# XMICRO-MEMORY.net
KiCad netlist of a schematic drawn in EAGLE
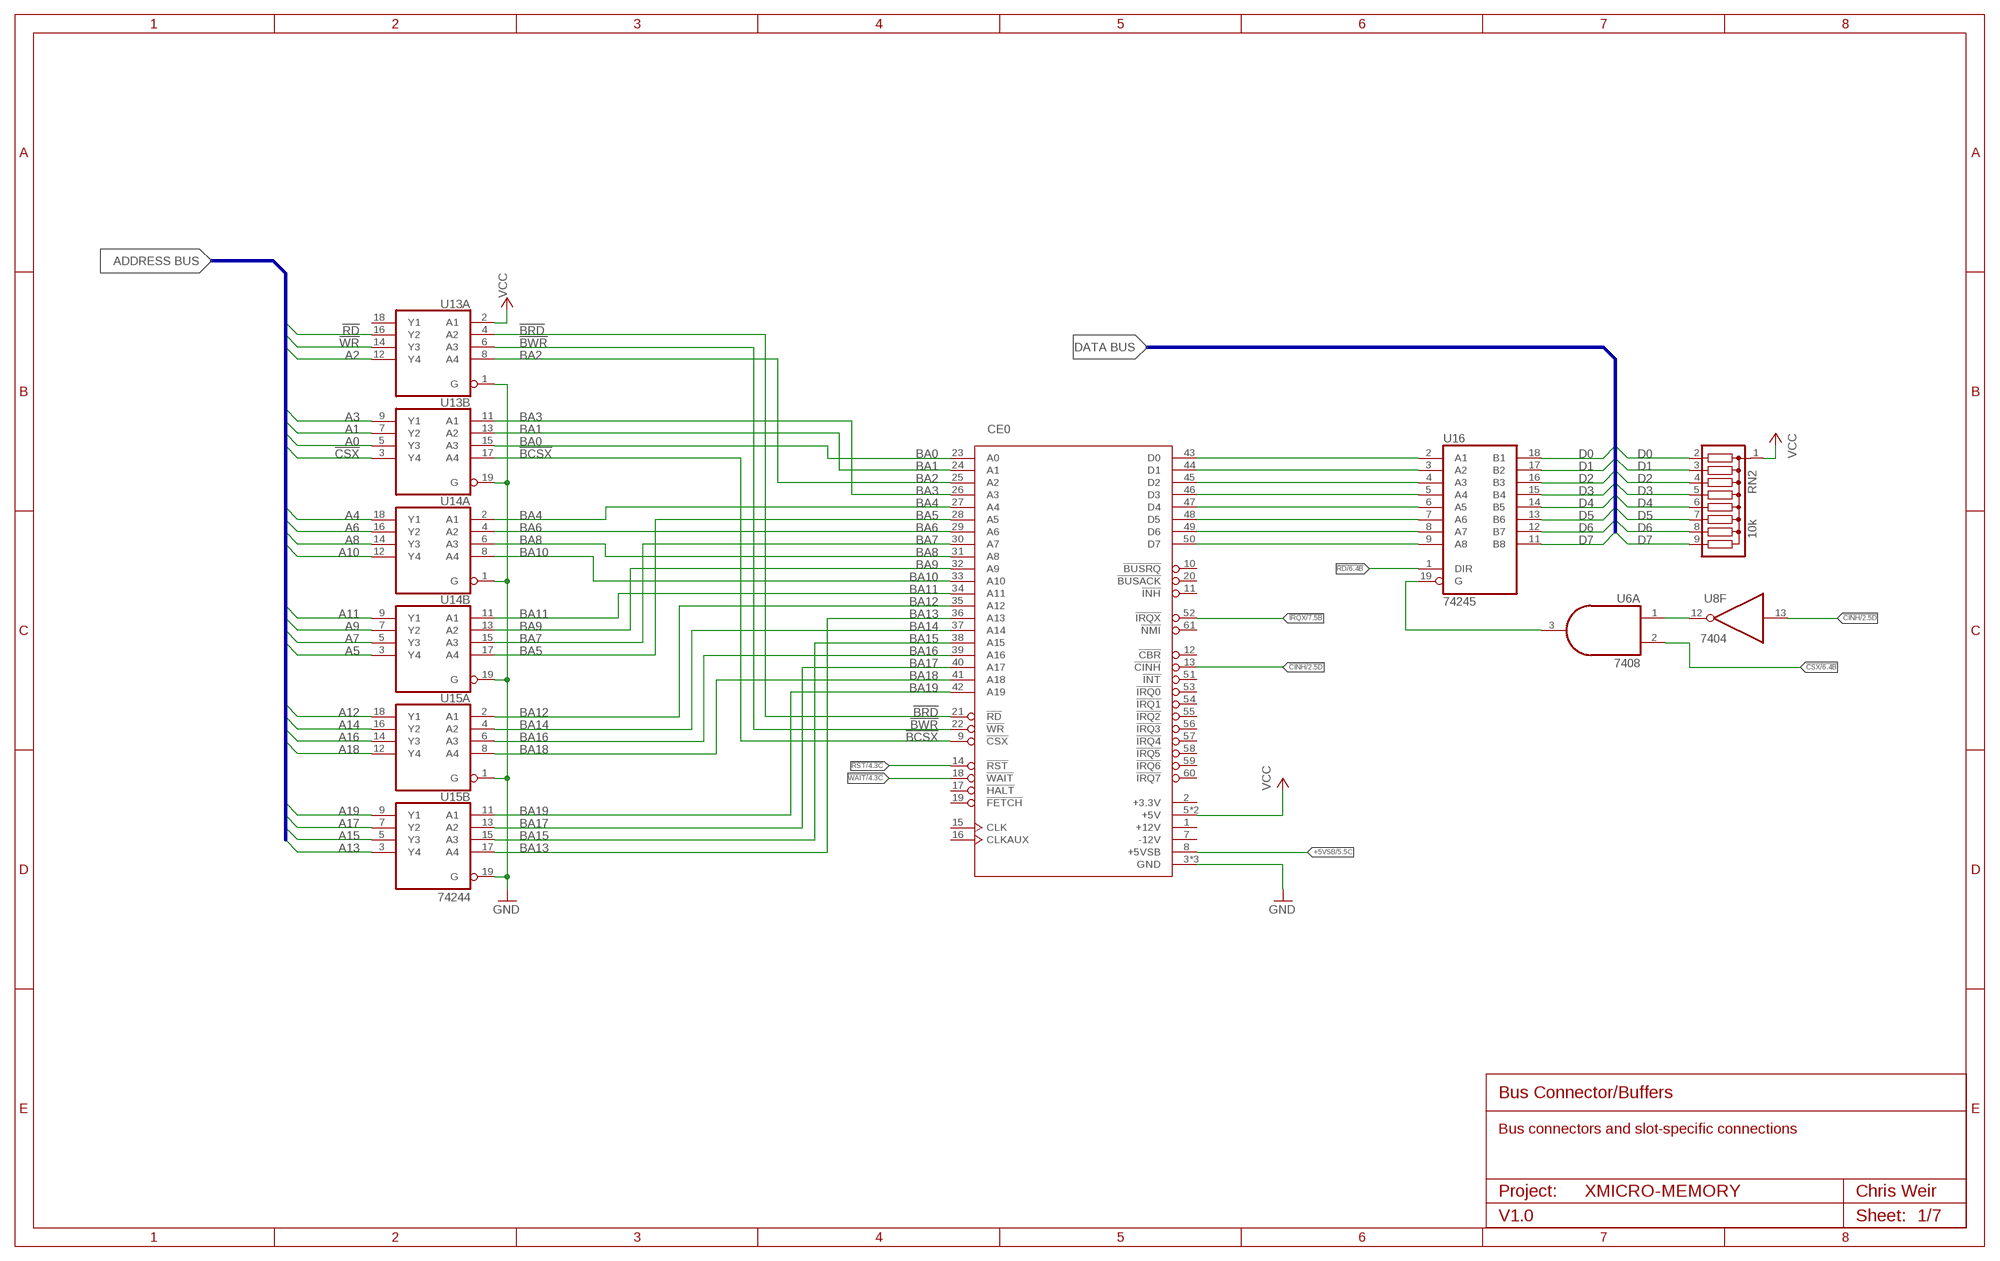
[diagram p0: schematic, sheet 1]
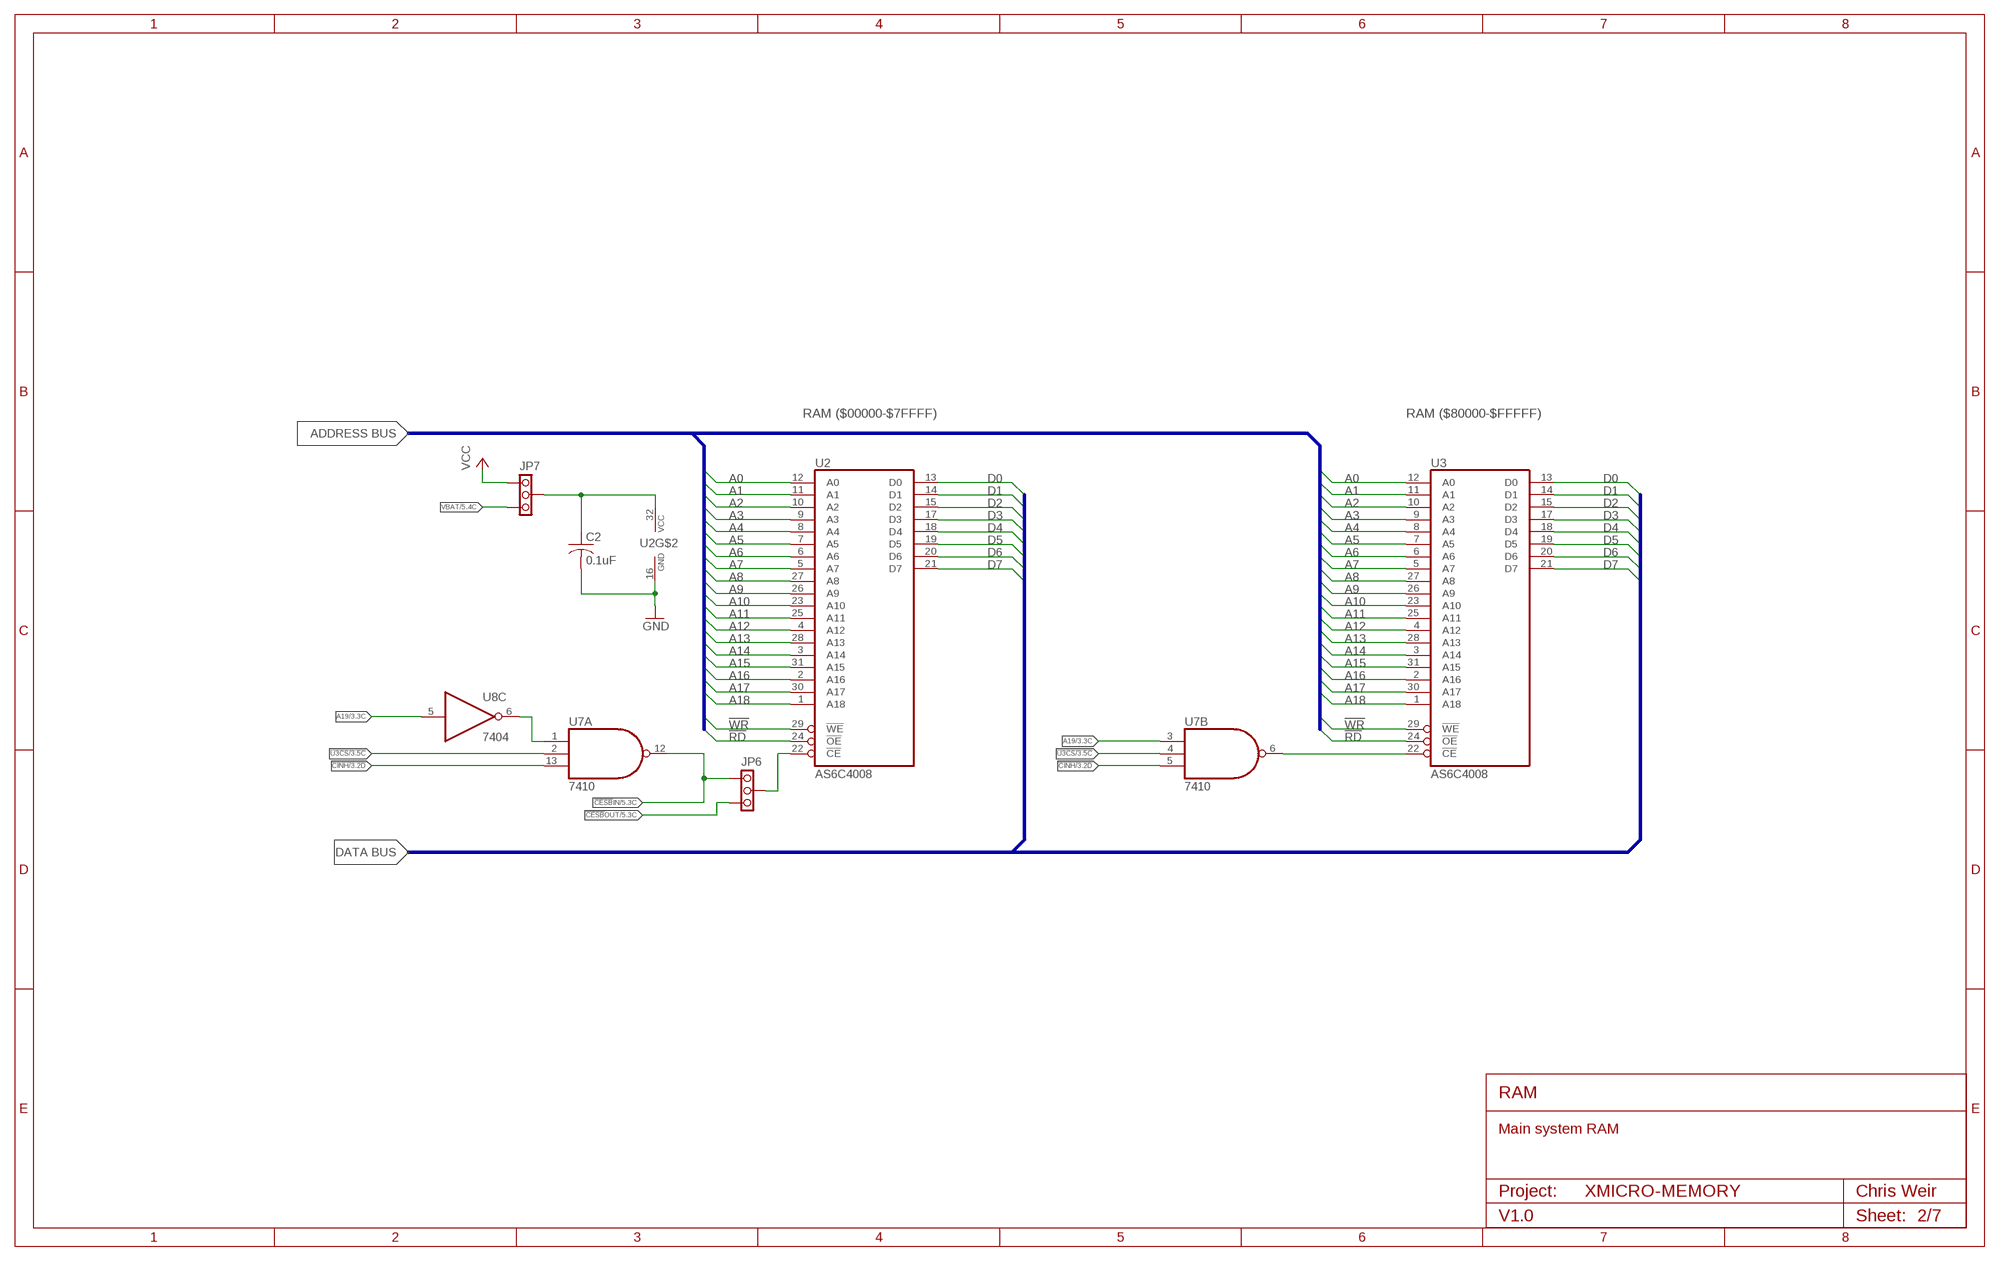
[diagram p1: schematic, sheet 2]
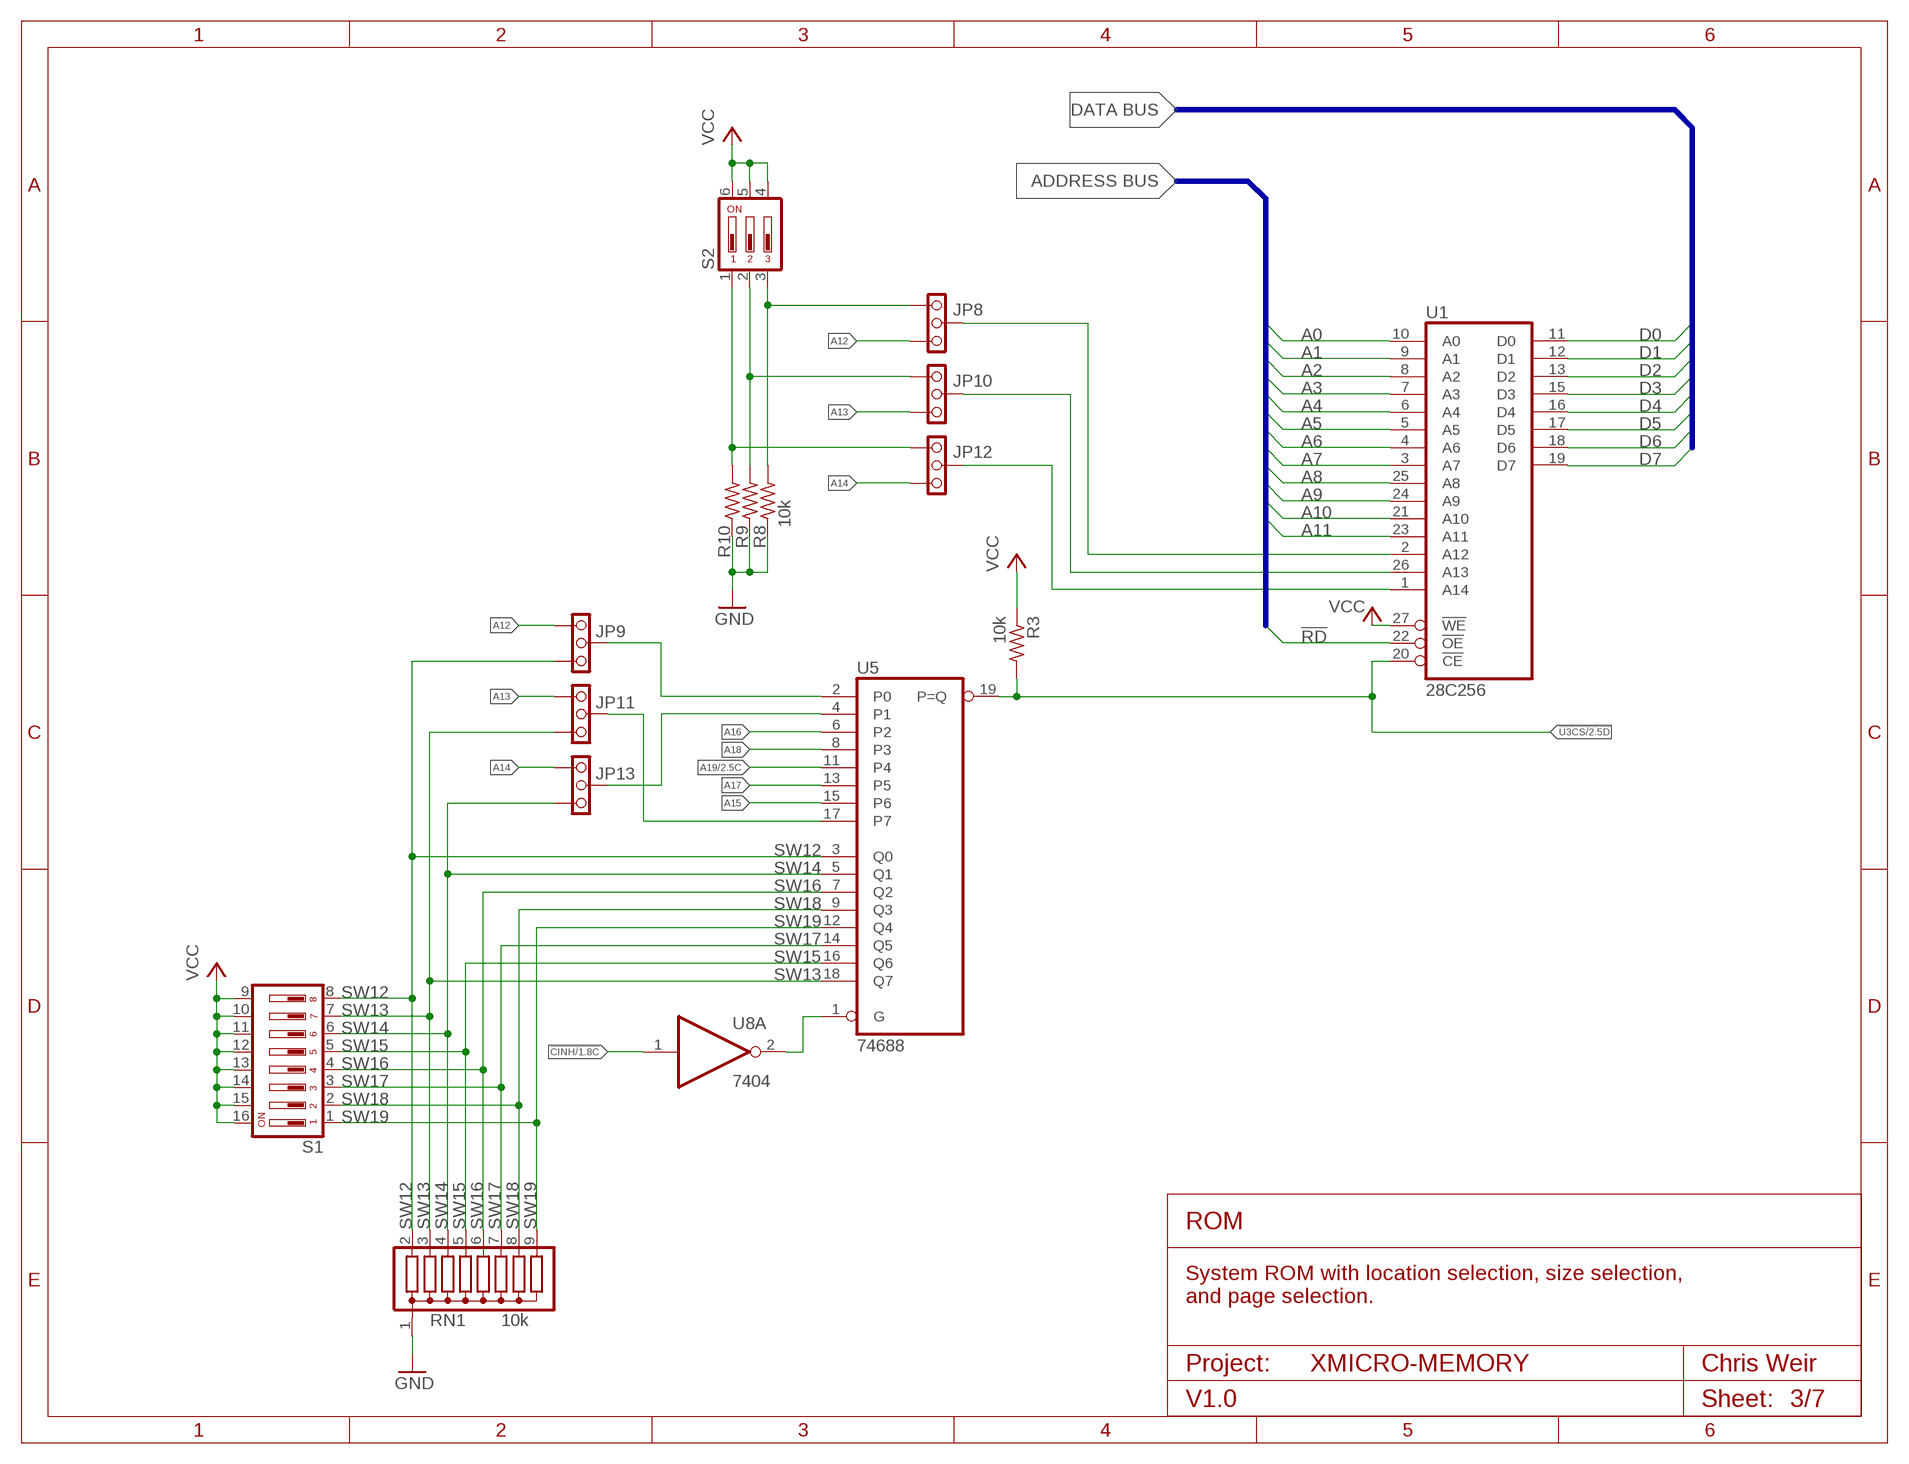
[diagram p2: schematic, sheet 3]
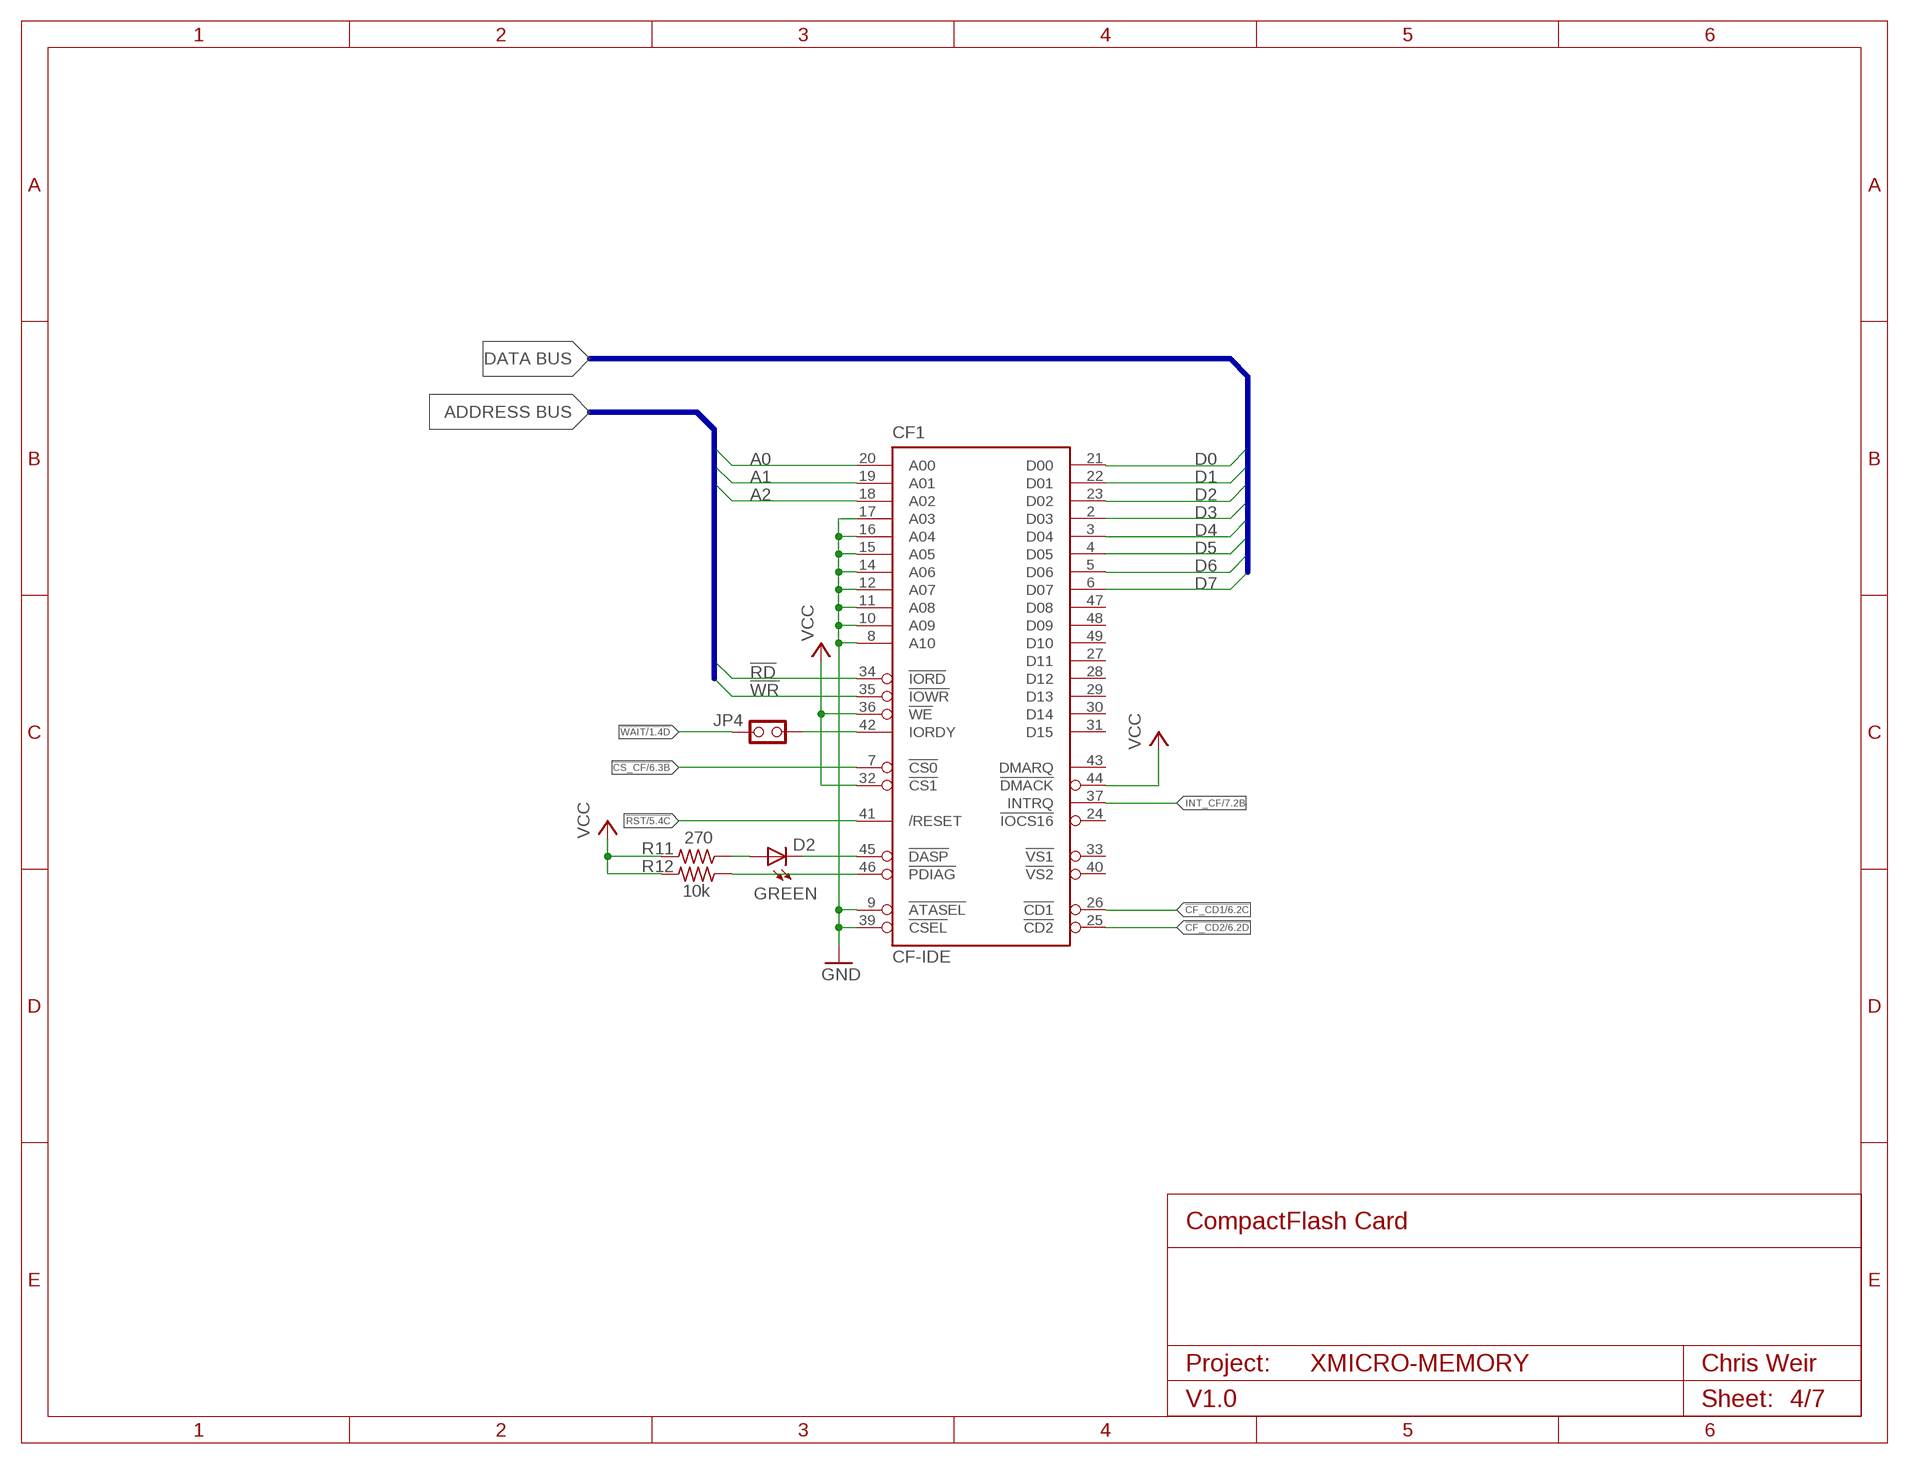
[diagram p3: schematic, sheet 4]
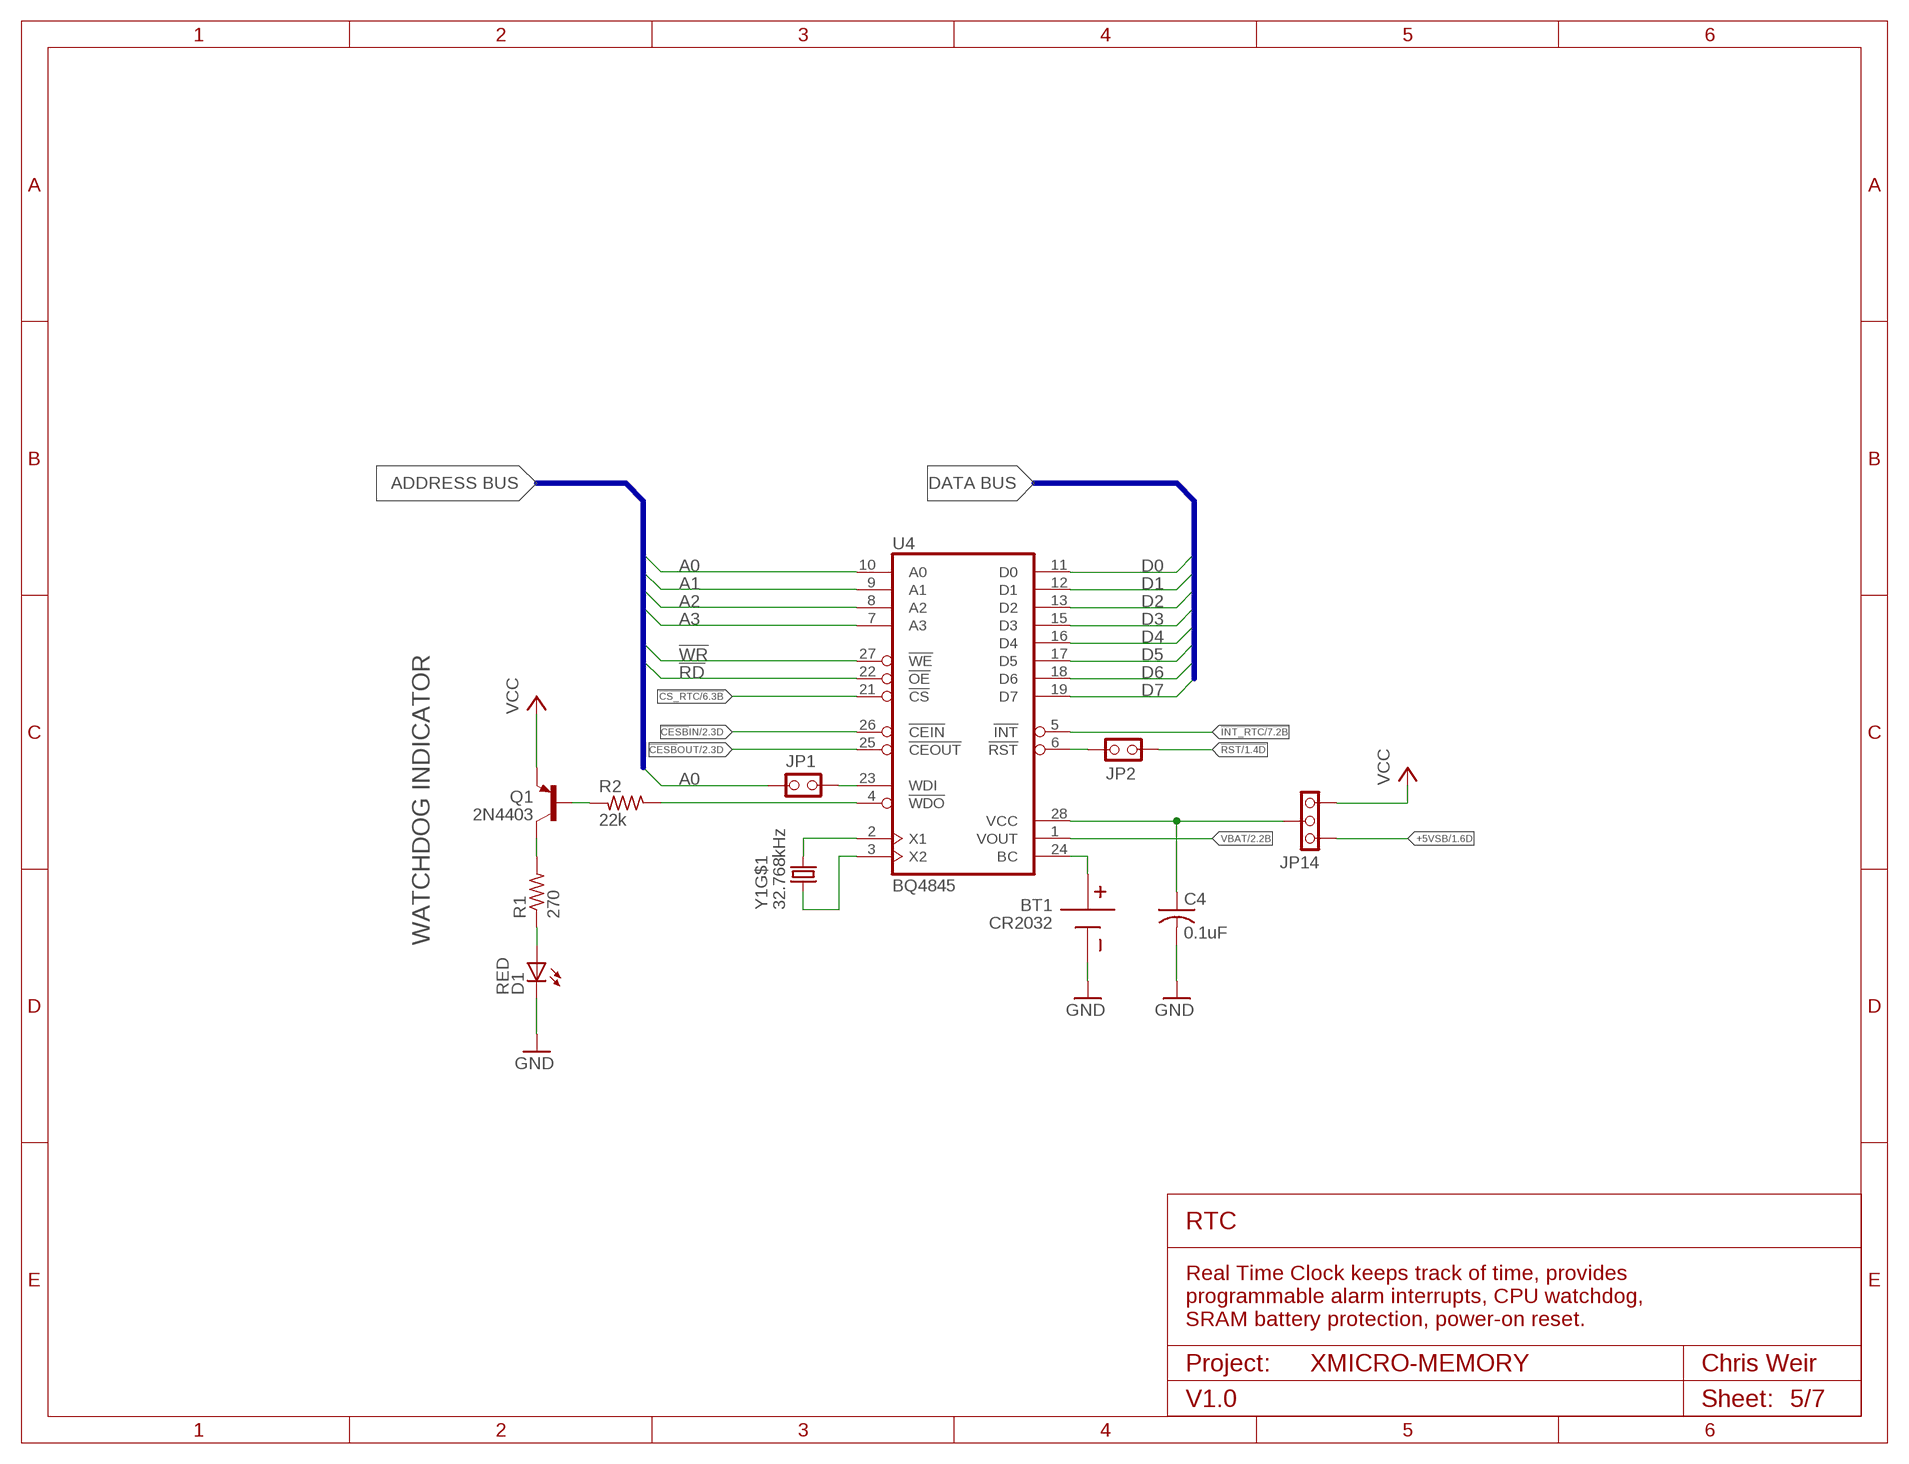
[diagram p4: schematic, sheet 5]
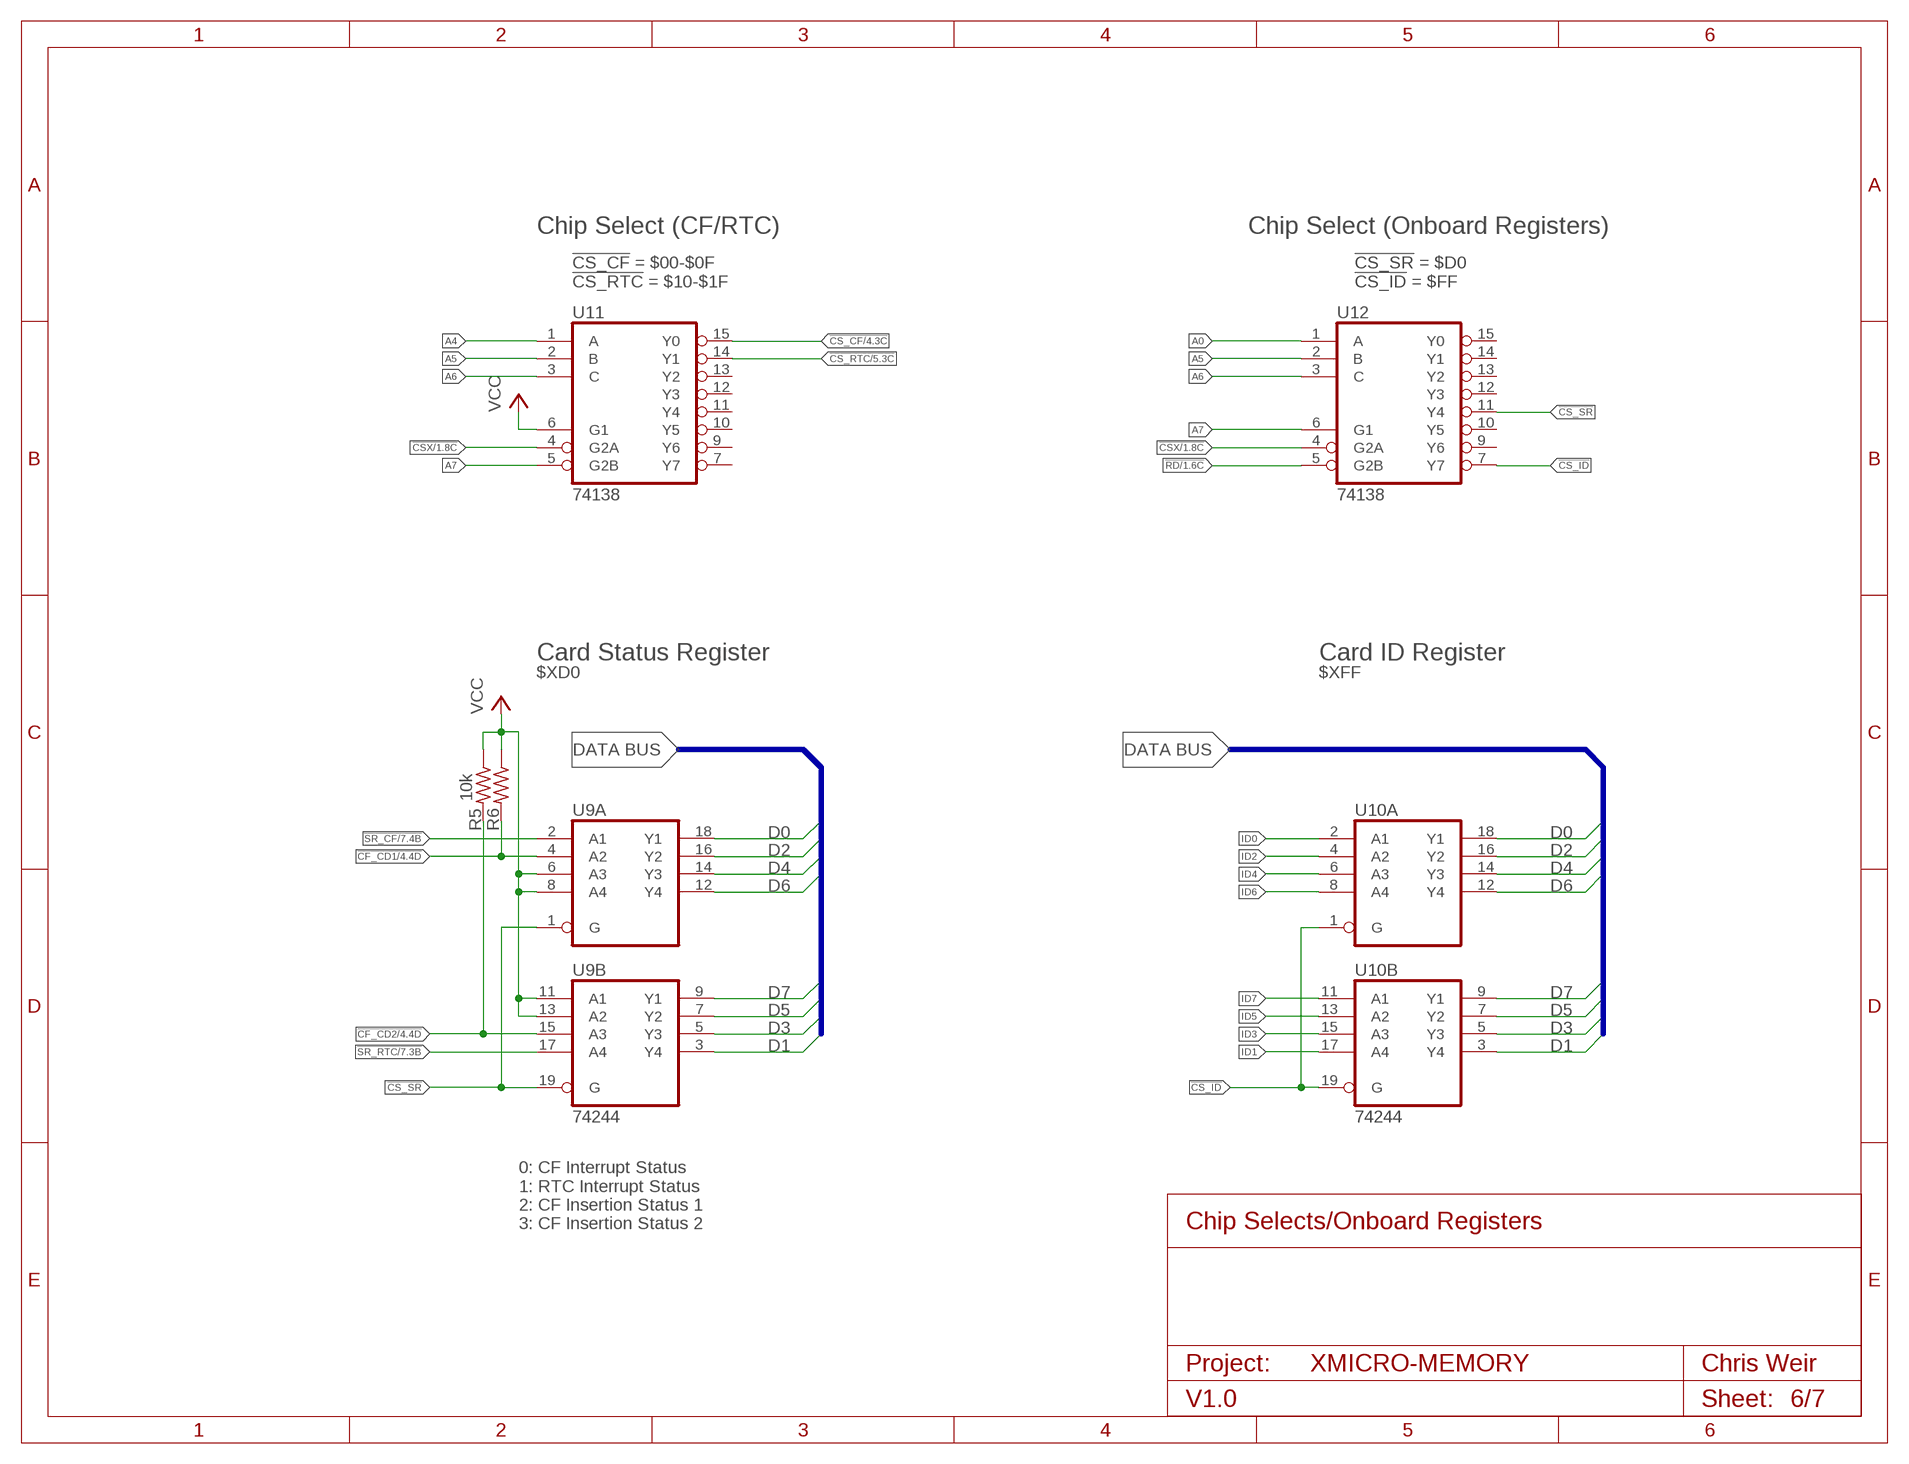
[diagram p5: schematic, sheet 6]
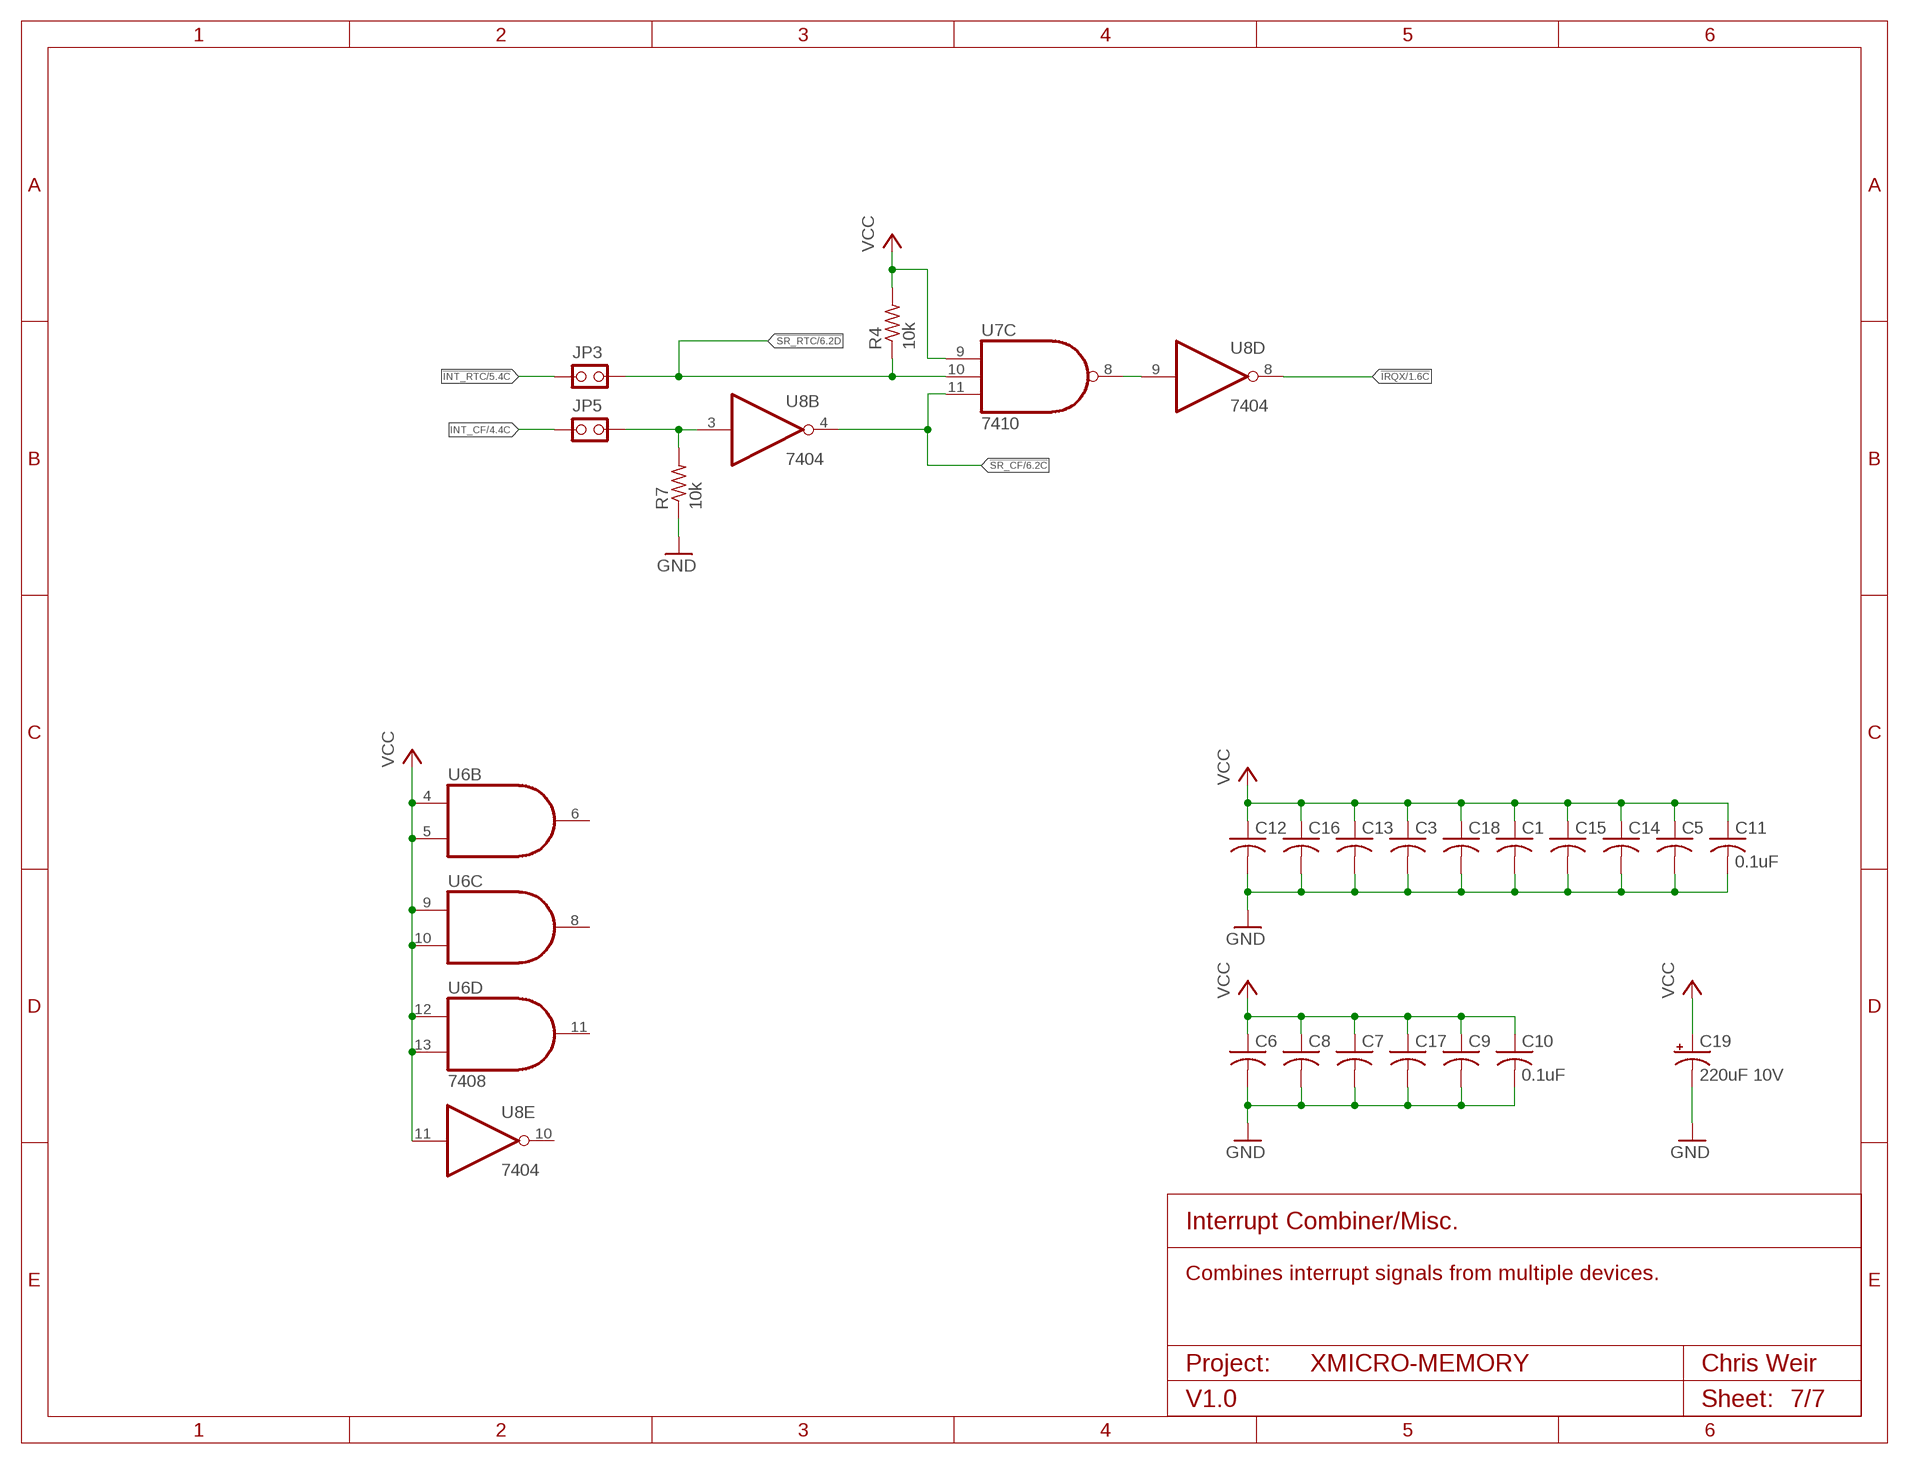
[diagram p6: schematic, sheet 7]

(export (version "E")
  (design (tool "Eeschema 10.0.6"))
  (components
    (comp (ref "BT1")
      (value "CR2032")
      (footprint "eagle-import:SMTU2032")
      (libsource (lib "eagle-import") (part "CR2032SMT"))
    )
    (comp (ref "C4")
      (value "0.1uF")
      (footprint "eagle-import:C025-024X044")
      (libsource (lib "eagle-import") (part "C-US025-024X044"))
    )
    (comp (ref "D1")
      (value "RED")
      (footprint "eagle-import:LED5MM")
      (libsource (lib "eagle-import") (part "LED5MM"))
    )
    (comp (ref "JP1")
      (value "PINHD-1X2THRU")
      (footprint "eagle-import:1X02")
      (libsource (lib "eagle-import") (part "PINHD-1X2THRU"))
    )
    (comp (ref "JP2")
      (value "PINHD-1X2THRU")
      (footprint "eagle-import:1X02")
      (libsource (lib "eagle-import") (part "PINHD-1X2THRU"))
    )
    (comp (ref "JP14")
      (value "PINHD1X3THRU")
      (footprint "eagle-import:1X03")
      (libsource (lib "eagle-import") (part "PINHD1X3THRU"))
    )
    (comp (ref "Q1")
      (value "2N4403")
      (footprint "eagle-import:TO92")
      (libsource (lib "eagle-import") (part "TRANSISTOR-PNP-2N4403"))
    )
    (comp (ref "R1")
      (value "270")
      (footprint "eagle-import:0207_10")
      (libsource (lib "eagle-import") (part "R-US_0207/10"))
    )
    (comp (ref "R2")
      (value "22k")
      (footprint "eagle-import:0207_10")
      (libsource (lib "eagle-import") (part "R-US_0207/10"))
    )
    (comp (ref "U4")
      (value "BQ4845")
      (footprint "eagle-import:DIL28")
      (libsource (lib "eagle-import") (part "BQ4845"))
    )
    (comp (ref "Y1")
      (value "32.768kHz")
      (footprint "eagle-import:CRYSTAL-3X8H")
      (libsource (lib "eagle-import") (part "CRYSTAL"))
    )
    (comp (ref "R5")
      (value "10k")
      (footprint "eagle-import:0207_10")
      (libsource (lib "eagle-import") (part "R-US_0207/10"))
    )
    (comp (ref "R6")
      (value "10k")
      (footprint "eagle-import:0207_10")
      (libsource (lib "eagle-import") (part "R-US_0207/10"))
    )
    (comp (ref "U9")
      (value "74244")
      (footprint "eagle-import:DIL20")
      (libsource (lib "eagle-import") (part "74244NLS"))
    )
    (comp (ref "U10")
      (value "74244")
      (footprint "eagle-import:DIL20")
      (libsource (lib "eagle-import") (part "74244NLS"))
    )
    (comp (ref "U11")
      (value "74138")
      (footprint "eagle-import:DIL16")
      (libsource (lib "eagle-import") (part "74138NLS"))
    )
    (comp (ref "U12")
      (value "74138")
      (footprint "eagle-import:DIL16")
      (libsource (lib "eagle-import") (part "74138NLS"))
    )
    (comp (ref "C1")
      (value "0.1uF")
      (footprint "eagle-import:C025-024X044")
      (libsource (lib "eagle-import") (part "C-US025-024X044"))
    )
    (comp (ref "C3")
      (value "0.1uF")
      (footprint "eagle-import:C025-024X044")
      (libsource (lib "eagle-import") (part "C-US025-024X044"))
    )
    (comp (ref "C5")
      (value "0.1uF")
      (footprint "eagle-import:C025-024X044")
      (libsource (lib "eagle-import") (part "C-US025-024X044"))
    )
    (comp (ref "C6")
      (value "0.1uF")
      (footprint "eagle-import:C025-024X044")
      (libsource (lib "eagle-import") (part "C-US025-024X044"))
    )
    (comp (ref "C7")
      (value "0.1uF")
      (footprint "eagle-import:C025-024X044")
      (libsource (lib "eagle-import") (part "C-US025-024X044"))
    )
    (comp (ref "C8")
      (value "0.1uF")
      (footprint "eagle-import:C025-024X044")
      (libsource (lib "eagle-import") (part "C-US025-024X044"))
    )
    (comp (ref "C9")
      (value "0.1uF")
      (footprint "eagle-import:C025-024X044")
      (libsource (lib "eagle-import") (part "C-US025-024X044"))
    )
    (comp (ref "C10")
      (value "0.1uF")
      (footprint "eagle-import:C025-024X044")
      (libsource (lib "eagle-import") (part "C-US025-024X044"))
    )
    (comp (ref "C11")
      (value "0.1uF")
      (footprint "eagle-import:C025-024X044")
      (libsource (lib "eagle-import") (part "C-US025-024X044"))
    )
    (comp (ref "C12")
      (value "0.1uF")
      (footprint "eagle-import:C025-024X044")
      (libsource (lib "eagle-import") (part "C-US025-024X044"))
    )
    (comp (ref "C13")
      (value "0.1uF")
      (footprint "eagle-import:C025-024X044")
      (libsource (lib "eagle-import") (part "C-US025-024X044"))
    )
    (comp (ref "C14")
      (value "0.1uF")
      (footprint "eagle-import:C025-024X044")
      (libsource (lib "eagle-import") (part "C-US025-024X044"))
    )
    (comp (ref "C15")
      (value "0.1uF")
      (footprint "eagle-import:C025-024X044")
      (libsource (lib "eagle-import") (part "C-US025-024X044"))
    )
    (comp (ref "C16")
      (value "0.1uF")
      (footprint "eagle-import:C025-024X044")
      (libsource (lib "eagle-import") (part "C-US025-024X044"))
    )
    (comp (ref "C17")
      (value "0.1uF")
      (footprint "eagle-import:C025-024X044")
      (libsource (lib "eagle-import") (part "C-US025-024X044"))
    )
    (comp (ref "C18")
      (value "0.1uF")
      (footprint "eagle-import:C025-024X044")
      (libsource (lib "eagle-import") (part "C-US025-024X044"))
    )
    (comp (ref "C19")
      (value "220uF 10V")
      (footprint "eagle-import:C-10-5")
      (libsource (lib "eagle-import") (part "CPOL-US-10-5"))
    )
    (comp (ref "JP3")
      (value "PINHD-1X2THRU")
      (footprint "eagle-import:1X02")
      (libsource (lib "eagle-import") (part "PINHD-1X2THRU"))
    )
    (comp (ref "JP5")
      (value "PINHD-1X2THRU")
      (footprint "eagle-import:1X02")
      (libsource (lib "eagle-import") (part "PINHD-1X2THRU"))
    )
    (comp (ref "R4")
      (value "10k")
      (footprint "eagle-import:0207_10")
      (libsource (lib "eagle-import") (part "R-US_0207/10"))
    )
    (comp (ref "R7")
      (value "10k")
      (footprint "eagle-import:0207_10")
      (libsource (lib "eagle-import") (part "R-US_0207/10"))
    )
    (comp (ref "U6")
      (value "7408")
      (footprint "eagle-import:DIL14")
      (libsource (lib "eagle-import") (part "7408NLS"))
    )
    (comp (ref "U7")
      (value "7410")
      (footprint "eagle-import:DIL14")
      (libsource (lib "eagle-import") (part "7410NLS"))
    )
    (comp (ref "U8")
      (value "7404")
      (footprint "eagle-import:DIL14")
      (libsource (lib "eagle-import") (part "7404NLS"))
    )
    (comp (ref "C2")
      (value "0.1uF")
      (footprint "eagle-import:C025-024X044")
      (libsource (lib "eagle-import") (part "C-US025-024X044"))
    )
    (comp (ref "JP6")
      (value "PINHD1X3THRU")
      (footprint "eagle-import:1X03")
      (libsource (lib "eagle-import") (part "PINHD1X3THRU"))
    )
    (comp (ref "JP7")
      (value "PINHD1X3THRU")
      (footprint "eagle-import:1X03")
      (libsource (lib "eagle-import") (part "PINHD1X3THRU"))
    )
    (comp (ref "U2")
      (value "AS6C4008")
      (footprint "eagle-import:DIL32-6")
      (libsource (lib "eagle-import") (part "4008"))
    )
    (comp (ref "U3")
      (value "AS6C4008")
      (footprint "eagle-import:DIL32-6")
      (libsource (lib "eagle-import") (part "4008"))
    )
    (comp (ref "JP8")
      (value "PINHD1X3THRU")
      (footprint "eagle-import:1X03")
      (libsource (lib "eagle-import") (part "PINHD1X3THRU"))
    )
    (comp (ref "JP9")
      (value "PINHD1X3THRU")
      (footprint "eagle-import:1X03")
      (libsource (lib "eagle-import") (part "PINHD1X3THRU"))
    )
    (comp (ref "JP10")
      (value "PINHD1X3THRU")
      (footprint "eagle-import:1X03")
      (libsource (lib "eagle-import") (part "PINHD1X3THRU"))
    )
    (comp (ref "JP11")
      (value "PINHD1X3THRU")
      (footprint "eagle-import:1X03")
      (libsource (lib "eagle-import") (part "PINHD1X3THRU"))
    )
    (comp (ref "JP12")
      (value "PINHD1X3THRU")
      (footprint "eagle-import:1X03")
      (libsource (lib "eagle-import") (part "PINHD1X3THRU"))
    )
    (comp (ref "JP13")
      (value "PINHD1X3THRU")
      (footprint "eagle-import:1X03")
      (libsource (lib "eagle-import") (part "PINHD1X3THRU"))
    )
    (comp (ref "R3")
      (value "10k")
      (footprint "eagle-import:0207_10")
      (libsource (lib "eagle-import") (part "R-US_0207/10"))
    )
    (comp (ref "R8")
      (value "10k")
      (footprint "eagle-import:0207_10")
      (libsource (lib "eagle-import") (part "R-US_0207/10"))
    )
    (comp (ref "R9")
      (value "10k")
      (footprint "eagle-import:0207_10")
      (libsource (lib "eagle-import") (part "R-US_0207/10"))
    )
    (comp (ref "R10")
      (value "10k")
      (footprint "eagle-import:0207_10")
      (libsource (lib "eagle-import") (part "R-US_0207/10"))
    )
    (comp (ref "RN1")
      (value "10k")
      (footprint "eagle-import:SIL9")
      (libsource (lib "eagle-import") (part "G08R"))
    )
    (comp (ref "S1")
      (value "SW-DIP08")
      (footprint "eagle-import:SW-DIP8")
      (libsource (lib "eagle-import") (part "SW-DIP08"))
    )
    (comp (ref "S2")
      (value "SW-DIP03")
      (footprint "eagle-import:SW-DIP3")
      (libsource (lib "eagle-import") (part "SW-DIP03"))
    )
    (comp (ref "U1")
      (value "28C256")
      (footprint "eagle-import:228-1277-00")
      (libsource (lib "eagle-import") (part "28256-ZIF28"))
    )
    (comp (ref "U5")
      (value "74688")
      (footprint "eagle-import:DIL20")
      (libsource (lib "eagle-import") (part "74688NLS"))
    )
    (comp (ref "CF1")
      (value "CF-IDE")
      (footprint "eagle-import:CF-KYOCERA")
      (libsource (lib "eagle-import") (part "CF-IDE"))
    )
    (comp (ref "D2")
      (value "GREEN")
      (footprint "eagle-import:LED-3-R")
      (libsource (lib "eagle-import") (part "LED-3-R"))
    )
    (comp (ref "JP4")
      (value "PINHD-1X2THRU")
      (footprint "eagle-import:1X02")
      (libsource (lib "eagle-import") (part "PINHD-1X2THRU"))
    )
    (comp (ref "R11")
      (value "270")
      (footprint "eagle-import:0207_10")
      (libsource (lib "eagle-import") (part "R-US_0207/10"))
    )
    (comp (ref "R12")
      (value "10k")
      (footprint "eagle-import:0207_10")
      (libsource (lib "eagle-import") (part "R-US_0207/10"))
    )
    (comp (ref "CE0")
      (value "XMICRO-BUS-EDGE62M")
      (footprint "eagle-import:EDGE62M")
      (libsource (lib "eagle-import") (part "XMICRO-BUS-EDGE62M"))
    )
    (comp (ref "RN2")
      (value "10k")
      (footprint "eagle-import:SIL9")
      (fields (field (name "OC_FARNELL") "unknown") (field (name "OC_NEWARK") "unknown"))
      (libsource (lib "eagle-import") (part "G08R"))
    )
    (comp (ref "U13")
      (value "74244")
      (footprint "eagle-import:DIL20")
      (libsource (lib "eagle-import") (part "74244NLS"))
    )
    (comp (ref "U14")
      (value "74244")
      (footprint "eagle-import:DIL20")
      (libsource (lib "eagle-import") (part "74244NLS"))
    )
    (comp (ref "U15")
      (value "74244")
      (footprint "eagle-import:DIL20")
      (libsource (lib "eagle-import") (part "74244NLS"))
    )
    (comp (ref "U16")
      (value "74245")
      (footprint "eagle-import:DIL20")
      (libsource (lib "eagle-import") (part "74245NLS"))
    )
  )
  (nets
    (net (code "1") (name "+5VSB") (class "Default")
      (node (ref "CE0") (pin "8") (pinfunction "+5VSB_8") (pintype "bidirectional"))
      (node (ref "JP14") (pin "1") (pinfunction "1_1") (pintype "passive"))
    )
    (net (code "3") (name "A0") (class "Default")
      (node (ref "CF1") (pin "20") (pinfunction "A00_20") (pintype "input"))
      (node (ref "JP1") (pin "1") (pinfunction "1_1") (pintype "passive"))
      (node (ref "U1") (pin "10") (pinfunction "A0_10") (pintype "input"))
      (node (ref "U12") (pin "1") (pinfunction "A_1") (pintype "input"))
      (node (ref "U13") (pin "5") (pinfunction "Y3_5") (pintype "tri_state"))
      (node (ref "U2") (pin "12") (pinfunction "A0_12") (pintype "input"))
      (node (ref "U3") (pin "12") (pinfunction "A0_12") (pintype "input"))
      (node (ref "U4") (pin "10") (pinfunction "A0_10") (pintype "input"))
    )
    (net (code "4") (name "A1") (class "Default")
      (node (ref "CF1") (pin "19") (pinfunction "A01_19") (pintype "input"))
      (node (ref "U1") (pin "9") (pinfunction "A1_9") (pintype "input"))
      (node (ref "U13") (pin "7") (pinfunction "Y2_7") (pintype "tri_state"))
      (node (ref "U2") (pin "11") (pinfunction "A1_11") (pintype "input"))
      (node (ref "U3") (pin "11") (pinfunction "A1_11") (pintype "input"))
      (node (ref "U4") (pin "9") (pinfunction "A1_9") (pintype "input"))
    )
    (net (code "5") (name "A2") (class "Default")
      (node (ref "CF1") (pin "18") (pinfunction "A02_18") (pintype "input"))
      (node (ref "U1") (pin "8") (pinfunction "A2_8") (pintype "input"))
      (node (ref "U13") (pin "12") (pinfunction "Y4_12") (pintype "tri_state"))
      (node (ref "U2") (pin "10") (pinfunction "A2_10") (pintype "input"))
      (node (ref "U3") (pin "10") (pinfunction "A2_10") (pintype "input"))
      (node (ref "U4") (pin "8") (pinfunction "A2_8") (pintype "input"))
    )
    (net (code "6") (name "A3") (class "Default")
      (node (ref "U1") (pin "7") (pinfunction "A3_7") (pintype "input"))
      (node (ref "U13") (pin "9") (pinfunction "Y1_9") (pintype "tri_state"))
      (node (ref "U2") (pin "9") (pinfunction "A3_9") (pintype "input"))
      (node (ref "U3") (pin "9") (pinfunction "A3_9") (pintype "input"))
      (node (ref "U4") (pin "7") (pinfunction "A3_7") (pintype "input"))
    )
    (net (code "7") (name "A4") (class "Default")
      (node (ref "U1") (pin "6") (pinfunction "A4_6") (pintype "input"))
      (node (ref "U11") (pin "1") (pinfunction "A_1") (pintype "input"))
      (node (ref "U14") (pin "18") (pinfunction "Y1_18") (pintype "tri_state"))
      (node (ref "U2") (pin "8") (pinfunction "A4_8") (pintype "input"))
      (node (ref "U3") (pin "8") (pinfunction "A4_8") (pintype "input"))
    )
    (net (code "8") (name "A5") (class "Default")
      (node (ref "U1") (pin "5") (pinfunction "A5_5") (pintype "input"))
      (node (ref "U11") (pin "2") (pinfunction "B_2") (pintype "input"))
      (node (ref "U12") (pin "2") (pinfunction "B_2") (pintype "input"))
      (node (ref "U14") (pin "3") (pinfunction "Y4_3") (pintype "tri_state"))
      (node (ref "U2") (pin "7") (pinfunction "A5_7") (pintype "input"))
      (node (ref "U3") (pin "7") (pinfunction "A5_7") (pintype "input"))
    )
    (net (code "9") (name "A6") (class "Default")
      (node (ref "U1") (pin "4") (pinfunction "A6_4") (pintype "input"))
      (node (ref "U11") (pin "3") (pinfunction "C_3") (pintype "input"))
      (node (ref "U12") (pin "3") (pinfunction "C_3") (pintype "input"))
      (node (ref "U14") (pin "16") (pinfunction "Y2_16") (pintype "tri_state"))
      (node (ref "U2") (pin "6") (pinfunction "A6_6") (pintype "input"))
      (node (ref "U3") (pin "6") (pinfunction "A6_6") (pintype "input"))
    )
    (net (code "10") (name "A7") (class "Default")
      (node (ref "U1") (pin "3") (pinfunction "A7_3") (pintype "input"))
      (node (ref "U11") (pin "5") (pinfunction "G2B_5") (pintype "input"))
      (node (ref "U12") (pin "6") (pinfunction "G1_6") (pintype "input"))
      (node (ref "U14") (pin "5") (pinfunction "Y3_5") (pintype "tri_state"))
      (node (ref "U2") (pin "5") (pinfunction "A7_5") (pintype "input"))
      (node (ref "U3") (pin "5") (pinfunction "A7_5") (pintype "input"))
    )
    (net (code "11") (name "A8") (class "Default")
      (node (ref "U1") (pin "25") (pinfunction "A8_25") (pintype "input"))
      (node (ref "U14") (pin "14") (pinfunction "Y3_14") (pintype "tri_state"))
      (node (ref "U2") (pin "27") (pinfunction "A8_27") (pintype "input"))
      (node (ref "U3") (pin "27") (pinfunction "A8_27") (pintype "input"))
    )
    (net (code "12") (name "A9") (class "Default")
      (node (ref "U1") (pin "24") (pinfunction "A9_24") (pintype "input"))
      (node (ref "U14") (pin "7") (pinfunction "Y2_7") (pintype "tri_state"))
      (node (ref "U2") (pin "26") (pinfunction "A9_26") (pintype "input"))
      (node (ref "U3") (pin "26") (pinfunction "A9_26") (pintype "input"))
    )
    (net (code "13") (name "A10") (class "Default")
      (node (ref "U1") (pin "21") (pinfunction "A10_21") (pintype "input"))
      (node (ref "U14") (pin "12") (pinfunction "Y4_12") (pintype "tri_state"))
      (node (ref "U2") (pin "23") (pinfunction "A10_23") (pintype "input"))
      (node (ref "U3") (pin "23") (pinfunction "A10_23") (pintype "input"))
    )
    (net (code "14") (name "A11") (class "Default")
      (node (ref "U1") (pin "23") (pinfunction "A11_23") (pintype "input"))
      (node (ref "U14") (pin "9") (pinfunction "Y1_9") (pintype "tri_state"))
      (node (ref "U2") (pin "25") (pinfunction "A11_25") (pintype "input"))
      (node (ref "U3") (pin "25") (pinfunction "A11_25") (pintype "input"))
    )
    (net (code "15") (name "A12") (class "Default")
      (node (ref "JP8") (pin "3") (pinfunction "3_3") (pintype "passive"))
      (node (ref "JP9") (pin "1") (pinfunction "1_1") (pintype "passive"))
      (node (ref "U15") (pin "18") (pinfunction "Y1_18") (pintype "tri_state"))
      (node (ref "U2") (pin "4") (pinfunction "A12_4") (pintype "input"))
      (node (ref "U3") (pin "4") (pinfunction "A12_4") (pintype "input"))
    )
    (net (code "16") (name "A13") (class "Default")
      (node (ref "JP10") (pin "3") (pinfunction "3_3") (pintype "passive"))
      (node (ref "JP11") (pin "1") (pinfunction "1_1") (pintype "passive"))
      (node (ref "U15") (pin "3") (pinfunction "Y4_3") (pintype "tri_state"))
      (node (ref "U2") (pin "28") (pinfunction "A13_28") (pintype "input"))
      (node (ref "U3") (pin "28") (pinfunction "A13_28") (pintype "input"))
    )
    (net (code "17") (name "A14") (class "Default")
      (node (ref "JP12") (pin "3") (pinfunction "3_3") (pintype "passive"))
      (node (ref "JP13") (pin "1") (pinfunction "1_1") (pintype "passive"))
      (node (ref "U15") (pin "16") (pinfunction "Y2_16") (pintype "tri_state"))
      (node (ref "U2") (pin "3") (pinfunction "A14_3") (pintype "input"))
      (node (ref "U3") (pin "3") (pinfunction "A14_3") (pintype "input"))
    )
    (net (code "18") (name "A15") (class "Default")
      (node (ref "U15") (pin "5") (pinfunction "Y3_5") (pintype "tri_state"))
      (node (ref "U2") (pin "31") (pinfunction "A15_31") (pintype "input"))
      (node (ref "U3") (pin "31") (pinfunction "A15_31") (pintype "input"))
      (node (ref "U5") (pin "15") (pinfunction "P6_15") (pintype "input"))
    )
    (net (code "19") (name "A16") (class "Default")
      (node (ref "U15") (pin "14") (pinfunction "Y3_14") (pintype "tri_state"))
      (node (ref "U2") (pin "2") (pinfunction "A16_2") (pintype "input"))
      (node (ref "U3") (pin "2") (pinfunction "A16_2") (pintype "input"))
      (node (ref "U5") (pin "6") (pinfunction "P2_6") (pintype "input"))
    )
    (net (code "20") (name "A17") (class "Default")
      (node (ref "U15") (pin "7") (pinfunction "Y2_7") (pintype "tri_state"))
      (node (ref "U2") (pin "30") (pinfunction "A17_30") (pintype "input"))
      (node (ref "U3") (pin "30") (pinfunction "A17_30") (pintype "input"))
      (node (ref "U5") (pin "13") (pinfunction "P5_13") (pintype "input"))
    )
    (net (code "21") (name "A18") (class "Default")
      (node (ref "U15") (pin "12") (pinfunction "Y4_12") (pintype "tri_state"))
      (node (ref "U2") (pin "1") (pinfunction "A18_1") (pintype "input"))
      (node (ref "U3") (pin "1") (pinfunction "A18_1") (pintype "input"))
      (node (ref "U5") (pin "8") (pinfunction "P3_8") (pintype "input"))
    )
    (net (code "22") (name "A19") (class "Default")
      (node (ref "U15") (pin "9") (pinfunction "Y1_9") (pintype "tri_state"))
      (node (ref "U5") (pin "11") (pinfunction "P4_11") (pintype "input"))
      (node (ref "U7") (pin "3") (pinfunction "I0_3") (pintype "input"))
      (node (ref "U8") (pin "5") (pinfunction "I_5") (pintype "input"))
    )
    (net (code "23") (name "BA0") (class "Default")
      (node (ref "CE0") (pin "23") (pinfunction "A0_23") (pintype "bidirectional"))
      (node (ref "U13") (pin "15") (pinfunction "A3_15") (pintype "input"))
    )
    (net (code "24") (name "BA1") (class "Default")
      (node (ref "CE0") (pin "24") (pinfunction "A1_24") (pintype "bidirectional"))
      (node (ref "U13") (pin "13") (pinfunction "A2_13") (pintype "input"))
    )
    (net (code "25") (name "BA2") (class "Default")
      (node (ref "CE0") (pin "25") (pinfunction "A2_25") (pintype "bidirectional"))
      (node (ref "U13") (pin "8") (pinfunction "A4_8") (pintype "input"))
    )
    (net (code "26") (name "BA3") (class "Default")
      (node (ref "CE0") (pin "26") (pinfunction "A3_26") (pintype "bidirectional"))
      (node (ref "U13") (pin "11") (pinfunction "A1_11") (pintype "input"))
    )
    (net (code "27") (name "BA4") (class "Default")
      (node (ref "CE0") (pin "27") (pinfunction "A4_27") (pintype "bidirectional"))
      (node (ref "U14") (pin "2") (pinfunction "A1_2") (pintype "input"))
    )
    (net (code "28") (name "BA5") (class "Default")
      (node (ref "CE0") (pin "28") (pinfunction "A5_28") (pintype "bidirectional"))
      (node (ref "U14") (pin "17") (pinfunction "A4_17") (pintype "input"))
    )
    (net (code "29") (name "BA6") (class "Default")
      (node (ref "CE0") (pin "29") (pinfunction "A6_29") (pintype "bidirectional"))
      (node (ref "U14") (pin "4") (pinfunction "A2_4") (pintype "input"))
    )
    (net (code "30") (name "BA7") (class "Default")
      (node (ref "CE0") (pin "30") (pinfunction "A7_30") (pintype "bidirectional"))
      (node (ref "U14") (pin "15") (pinfunction "A3_15") (pintype "input"))
    )
    (net (code "31") (name "BA8") (class "Default")
      (node (ref "CE0") (pin "31") (pinfunction "A8_31") (pintype "bidirectional"))
      (node (ref "U14") (pin "6") (pinfunction "A3_6") (pintype "input"))
    )
    (net (code "32") (name "BA9") (class "Default")
      (node (ref "CE0") (pin "32") (pinfunction "A9_32") (pintype "bidirectional"))
      (node (ref "U14") (pin "13") (pinfunction "A2_13") (pintype "input"))
    )
    (net (code "33") (name "BA10") (class "Default")
      (node (ref "CE0") (pin "33") (pinfunction "A10_33") (pintype "bidirectional"))
      (node (ref "U14") (pin "8") (pinfunction "A4_8") (pintype "input"))
    )
    (net (code "34") (name "BA11") (class "Default")
      (node (ref "CE0") (pin "34") (pinfunction "A11_34") (pintype "bidirectional"))
      (node (ref "U14") (pin "11") (pinfunction "A1_11") (pintype "input"))
    )
    (net (code "35") (name "BA12") (class "Default")
      (node (ref "CE0") (pin "35") (pinfunction "A12_35") (pintype "bidirectional"))
      (node (ref "U15") (pin "2") (pinfunction "A1_2") (pintype "input"))
    )
    (net (code "36") (name "BA13") (class "Default")
      (node (ref "CE0") (pin "36") (pinfunction "A13_36") (pintype "bidirectional"))
      (node (ref "U15") (pin "17") (pinfunction "A4_17") (pintype "input"))
    )
    (net (code "37") (name "BA14") (class "Default")
      (node (ref "CE0") (pin "37") (pinfunction "A14_37") (pintype "bidirectional"))
      (node (ref "U15") (pin "4") (pinfunction "A2_4") (pintype "input"))
    )
    (net (code "38") (name "BA15") (class "Default")
      (node (ref "CE0") (pin "38") (pinfunction "A15_38") (pintype "bidirectional"))
      (node (ref "U15") (pin "15") (pinfunction "A3_15") (pintype "input"))
    )
    (net (code "39") (name "BA16") (class "Default")
      (node (ref "CE0") (pin "39") (pinfunction "A16_39") (pintype "bidirectional"))
      (node (ref "U15") (pin "6") (pinfunction "A3_6") (pintype "input"))
    )
    (net (code "40") (name "BA17") (class "Default")
      (node (ref "CE0") (pin "40") (pinfunction "A17_40") (pintype "bidirectional"))
      (node (ref "U15") (pin "13") (pinfunction "A2_13") (pintype "input"))
    )
    (net (code "41") (name "BA18") (class "Default")
      (node (ref "CE0") (pin "41") (pinfunction "A18_41") (pintype "bidirectional"))
      (node (ref "U15") (pin "8") (pinfunction "A4_8") (pintype "input"))
    )
    (net (code "42") (name "BA19") (class "Default")
      (node (ref "CE0") (pin "42") (pinfunction "A19_42") (pintype "bidirectional"))
      (node (ref "U15") (pin "11") (pinfunction "A1_11") (pintype "input"))
    )
    (net (code "43") (name "D0") (class "Default")
      (node (ref "CF1") (pin "21") (pinfunction "D00_21") (pintype "tri_state"))
      (node (ref "RN2") (pin "2") (pinfunction "2_2") (pintype "passive"))
      (node (ref "U1") (pin "11") (pinfunction "D0_11") (pintype "tri_state"))
      (node (ref "U10") (pin "18") (pinfunction "Y1_18") (pintype "tri_state"))
      (node (ref "U16") (pin "18") (pinfunction "B1_18") (pintype "bidirectional"))
      (node (ref "U2") (pin "13") (pinfunction "D0_13") (pintype "tri_state"))
      (node (ref "U3") (pin "13") (pinfunction "D0_13") (pintype "tri_state"))
      (node (ref "U4") (pin "11") (pinfunction "D0_11") (pintype "tri_state"))
      (node (ref "U9") (pin "18") (pinfunction "Y1_18") (pintype "tri_state"))
    )
    (net (code "44") (name "D1") (class "Default")
      (node (ref "CF1") (pin "22") (pinfunction "D01_22") (pintype "tri_state"))
      (node (ref "RN2") (pin "3") (pinfunction "3_3") (pintype "passive"))
      (node (ref "U1") (pin "12") (pinfunction "D1_12") (pintype "tri_state"))
      (node (ref "U10") (pin "3") (pinfunction "Y4_3") (pintype "tri_state"))
      (node (ref "U16") (pin "17") (pinfunction "B2_17") (pintype "bidirectional"))
      (node (ref "U2") (pin "14") (pinfunction "D1_14") (pintype "tri_state"))
      (node (ref "U3") (pin "14") (pinfunction "D1_14") (pintype "tri_state"))
      (node (ref "U4") (pin "12") (pinfunction "D1_12") (pintype "tri_state"))
      (node (ref "U9") (pin "3") (pinfunction "Y4_3") (pintype "tri_state"))
    )
    (net (code "45") (name "D2") (class "Default")
      (node (ref "CF1") (pin "23") (pinfunction "D02_23") (pintype "tri_state"))
      (node (ref "RN2") (pin "4") (pinfunction "4_4") (pintype "passive"))
      (node (ref "U1") (pin "13") (pinfunction "D2_13") (pintype "tri_state"))
      (node (ref "U10") (pin "16") (pinfunction "Y2_16") (pintype "tri_state"))
      (node (ref "U16") (pin "16") (pinfunction "B3_16") (pintype "bidirectional"))
      (node (ref "U2") (pin "15") (pinfunction "D2_15") (pintype "tri_state"))
      (node (ref "U3") (pin "15") (pinfunction "D2_15") (pintype "tri_state"))
      (node (ref "U4") (pin "13") (pinfunction "D2_13") (pintype "tri_state"))
      (node (ref "U9") (pin "16") (pinfunction "Y2_16") (pintype "tri_state"))
    )
    (net (code "46") (name "D3") (class "Default")
      (node (ref "CF1") (pin "2") (pinfunction "D03_2") (pintype "tri_state"))
      (node (ref "RN2") (pin "5") (pinfunction "5_5") (pintype "passive"))
      (node (ref "U1") (pin "15") (pinfunction "D3_15") (pintype "tri_state"))
      (node (ref "U10") (pin "5") (pinfunction "Y3_5") (pintype "tri_state"))
      (node (ref "U16") (pin "15") (pinfunction "B4_15") (pintype "bidirectional"))
      (node (ref "U2") (pin "17") (pinfunction "D3_17") (pintype "tri_state"))
      (node (ref "U3") (pin "17") (pinfunction "D3_17") (pintype "tri_state"))
      (node (ref "U4") (pin "15") (pinfunction "D3_15") (pintype "tri_state"))
      (node (ref "U9") (pin "5") (pinfunction "Y3_5") (pintype "tri_state"))
    )
    (net (code "47") (name "D4") (class "Default")
      (node (ref "CF1") (pin "3") (pinfunction "D04_3") (pintype "tri_state"))
      (node (ref "RN2") (pin "6") (pinfunction "6_6") (pintype "passive"))
      (node (ref "U1") (pin "16") (pinfunction "D4_16") (pintype "tri_state"))
      (node (ref "U10") (pin "14") (pinfunction "Y3_14") (pintype "tri_state"))
      (node (ref "U16") (pin "14") (pinfunction "B5_14") (pintype "bidirectional"))
      (node (ref "U2") (pin "18") (pinfunction "D4_18") (pintype "tri_state"))
      (node (ref "U3") (pin "18") (pinfunction "D4_18") (pintype "tri_state"))
      (node (ref "U4") (pin "16") (pinfunction "D4_16") (pintype "tri_state"))
      (node (ref "U9") (pin "14") (pinfunction "Y3_14") (pintype "tri_state"))
    )
    (net (code "48") (name "D5") (class "Default")
      (node (ref "CF1") (pin "4") (pinfunction "D05_4") (pintype "tri_state"))
      (node (ref "RN2") (pin "7") (pinfunction "7_7") (pintype "passive"))
      (node (ref "U1") (pin "17") (pinfunction "D5_17") (pintype "tri_state"))
      (node (ref "U10") (pin "7") (pinfunction "Y2_7") (pintype "tri_state"))
      (node (ref "U16") (pin "13") (pinfunction "B6_13") (pintype "bidirectional"))
      (node (ref "U2") (pin "19") (pinfunction "D5_19") (pintype "tri_state"))
      (node (ref "U3") (pin "19") (pinfunction "D5_19") (pintype "tri_state"))
      (node (ref "U4") (pin "17") (pinfunction "D5_17") (pintype "tri_state"))
      (node (ref "U9") (pin "7") (pinfunction "Y2_7") (pintype "tri_state"))
    )
    (net (code "49") (name "D6") (class "Default")
      (node (ref "CF1") (pin "5") (pinfunction "D06_5") (pintype "tri_state"))
      (node (ref "RN2") (pin "8") (pinfunction "8_8") (pintype "passive"))
      (node (ref "U1") (pin "18") (pinfunction "D6_18") (pintype "tri_state"))
      (node (ref "U10") (pin "12") (pinfunction "Y4_12") (pintype "tri_state"))
      (node (ref "U16") (pin "12") (pinfunction "B7_12") (pintype "bidirectional"))
      (node (ref "U2") (pin "20") (pinfunction "D6_20") (pintype "tri_state"))
      (node (ref "U3") (pin "20") (pinfunction "D6_20") (pintype "tri_state"))
      (node (ref "U4") (pin "18") (pinfunction "D6_18") (pintype "tri_state"))
      (node (ref "U9") (pin "12") (pinfunction "Y4_12") (pintype "tri_state"))
    )
    (net (code "50") (name "D7") (class "Default")
      (node (ref "CF1") (pin "6") (pinfunction "D07_6") (pintype "tri_state"))
      (node (ref "RN2") (pin "9") (pinfunction "9_9") (pintype "passive"))
      (node (ref "U1") (pin "19") (pinfunction "D7_19") (pintype "tri_state"))
      (node (ref "U10") (pin "9") (pinfunction "Y1_9") (pintype "tri_state"))
      (node (ref "U16") (pin "11") (pinfunction "B8_11") (pintype "bidirectional"))
      (node (ref "U2") (pin "21") (pinfunction "D7_21") (pintype "tri_state"))
      (node (ref "U3") (pin "21") (pinfunction "D7_21") (pintype "tri_state"))
      (node (ref "U4") (pin "19") (pinfunction "D7_19") (pintype "tri_state"))
      (node (ref "U9") (pin "9") (pinfunction "Y1_9") (pintype "tri_state"))
    )
    (net (code "51") (name "GND") (class "Default")
      (node (ref "BT1") (pin "-") (pinfunction "-_-") (pintype "passive"))
      (node (ref "C1") (pin "2") (pinfunction "2_2") (pintype "passive"))
      (node (ref "C10") (pin "2") (pinfunction "2_2") (pintype "passive"))
      (node (ref "C11") (pin "2") (pinfunction "2_2") (pintype "passive"))
      (node (ref "C12") (pin "2") (pinfunction "2_2") (pintype "passive"))
      (node (ref "C13") (pin "2") (pinfunction "2_2") (pintype "passive"))
      (node (ref "C14") (pin "2") (pinfunction "2_2") (pintype "passive"))
      (node (ref "C15") (pin "2") (pinfunction "2_2") (pintype "passive"))
      (node (ref "C16") (pin "2") (pinfunction "2_2") (pintype "passive"))
      (node (ref "C17") (pin "2") (pinfunction "2_2") (pintype "passive"))
      (node (ref "C18") (pin "2") (pinfunction "2_2") (pintype "passive"))
      (node (ref "C19") (pin "-") (pinfunction "-_-") (pintype "passive"))
      (node (ref "C2") (pin "2") (pinfunction "2_2") (pintype "passive"))
      (node (ref "C3") (pin "2") (pinfunction "2_2") (pintype "passive"))
      (node (ref "C4") (pin "2") (pinfunction "2_2") (pintype "passive"))
      (node (ref "C5") (pin "2") (pinfunction "2_2") (pintype "passive"))
      (node (ref "C6") (pin "2") (pinfunction "2_2") (pintype "passive"))
      (node (ref "C7") (pin "2") (pinfunction "2_2") (pintype "passive"))
      (node (ref "C8") (pin "2") (pinfunction "2_2") (pintype "passive"))
      (node (ref "C9") (pin "2") (pinfunction "2_2") (pintype "passive"))
      (node (ref "CE0") (pin "3") (pinfunction "GND_3") (pintype "bidirectional"))
      (node (ref "CE0") (pin "4") (pinfunction "GND_4") (pintype "bidirectional"))
      (node (ref "CE0") (pin "62") (pinfunction "GND_62") (pintype "bidirectional"))
      (node (ref "CF1") (pin "10") (pinfunction "A09_10") (pintype "input"))
      (node (ref "CF1") (pin "11") (pinfunction "A08_11") (pintype "input"))
      (node (ref "CF1") (pin "12") (pinfunction "A07_12") (pintype "input"))
      (node (ref "CF1") (pin "14") (pinfunction "A06_14") (pintype "input"))
      (node (ref "CF1") (pin "15") (pinfunction "A05_15") (pintype "input"))
      (node (ref "CF1") (pin "16") (pinfunction "A04_16") (pintype "input"))
      (node (ref "CF1") (pin "17") (pinfunction "A03_17") (pintype "input"))
      (node (ref "CF1") (pin "39") (pinfunction "~{CSEL}_39") (pintype "input"))
      (node (ref "CF1") (pin "8") (pinfunction "A10_8") (pintype "input"))
      (node (ref "CF1") (pin "9") (pinfunction "~{ATASEL}_9") (pintype "input"))
      (node (ref "D1") (pin "K") (pinfunction "C_K") (pintype "passive"))
      (node (ref "R10") (pin "1") (pinfunction "1_1") (pintype "passive"))
      (node (ref "R7") (pin "1") (pinfunction "1_1") (pintype "passive"))
      (node (ref "R8") (pin "1") (pinfunction "1_1") (pintype "passive"))
      (node (ref "R9") (pin "1") (pinfunction "1_1") (pintype "passive"))
      (node (ref "RN1") (pin "1") (pinfunction "1_1") (pintype "passive"))
      (node (ref "U13") (pin "1") (pinfunction "G_1") (pintype "input"))
      (node (ref "U13") (pin "19") (pinfunction "G_19") (pintype "input"))
      (node (ref "U14") (pin "1") (pinfunction "G_1") (pintype "input"))
      (node (ref "U14") (pin "19") (pinfunction "G_19") (pintype "input"))
      (node (ref "U15") (pin "1") (pinfunction "G_1") (pintype "input"))
      (node (ref "U15") (pin "19") (pinfunction "G_19") (pintype "input"))
      (node (ref "U2") (pin "16") (pinfunction "GND_16") (pintype "power_in"))
    )
    (net (code "52") (name "ID0") (class "Default")
      (node (ref "U10") (pin "2") (pinfunction "A1_2") (pintype "input"))
    )
    (net (code "53") (name "ID1") (class "Default")
      (node (ref "U10") (pin "17") (pinfunction "A4_17") (pintype "input"))
    )
    (net (code "54") (name "ID2") (class "Default")
      (node (ref "U10") (pin "4") (pinfunction "A2_4") (pintype "input"))
    )
    (net (code "55") (name "ID3") (class "Default")
      (node (ref "U10") (pin "15") (pinfunction "A3_15") (pintype "input"))
    )
    (net (code "56") (name "ID4") (class "Default")
      (node (ref "U10") (pin "6") (pinfunction "A3_6") (pintype "input"))
    )
    (net (code "57") (name "ID5") (class "Default")
      (node (ref "U10") (pin "13") (pinfunction "A2_13") (pintype "input"))
    )
    (net (code "58") (name "ID6") (class "Default")
      (node (ref "U10") (pin "8") (pinfunction "A4_8") (pintype "input"))
    )
    (net (code "59") (name "ID7") (class "Default")
      (node (ref "U10") (pin "11") (pinfunction "A1_11") (pintype "input"))
    )
    (net (code "60") (name "INT_CF") (class "Default")
      (node (ref "CF1") (pin "37") (pinfunction "INTRQ_37") (pintype "output"))
      (node (ref "JP5") (pin "1") (pinfunction "1_1") (pintype "passive"))
    )
    (net (code "61") (name "Net-(CE0-D0)") (class "Default")
      (node (ref "CE0") (pin "43") (pinfunction "D0_43") (pintype "bidirectional"))
      (node (ref "U16") (pin "2") (pinfunction "A1_2") (pintype "bidirectional"))
    )
    (net (code "62") (name "Net-(CE0-D1)") (class "Default")
      (node (ref "CE0") (pin "44") (pinfunction "D1_44") (pintype "bidirectional"))
      (node (ref "U16") (pin "3") (pinfunction "A2_3") (pintype "bidirectional"))
    )
    (net (code "63") (name "Net-(CE0-D2)") (class "Default")
      (node (ref "CE0") (pin "45") (pinfunction "D2_45") (pintype "bidirectional"))
      (node (ref "U16") (pin "4") (pinfunction "A3_4") (pintype "bidirectional"))
    )
    (net (code "64") (name "Net-(CE0-D3)") (class "Default")
      (node (ref "CE0") (pin "46") (pinfunction "D3_46") (pintype "bidirectional"))
      (node (ref "U16") (pin "5") (pinfunction "A4_5") (pintype "bidirectional"))
    )
    (net (code "65") (name "Net-(CE0-D4)") (class "Default")
      (node (ref "CE0") (pin "47") (pinfunction "D4_47") (pintype "bidirectional"))
      (node (ref "U16") (pin "6") (pinfunction "A5_6") (pintype "bidirectional"))
    )
    (net (code "66") (name "Net-(CE0-D5)") (class "Default")
      (node (ref "CE0") (pin "48") (pinfunction "D5_48") (pintype "bidirectional"))
      (node (ref "U16") (pin "7") (pinfunction "A6_7") (pintype "bidirectional"))
    )
    (net (code "67") (name "Net-(CE0-D6)") (class "Default")
      (node (ref "CE0") (pin "49") (pinfunction "D6_49") (pintype "bidirectional"))
      (node (ref "U16") (pin "8") (pinfunction "A7_8") (pintype "bidirectional"))
    )
    (net (code "68") (name "Net-(CE0-D7)") (class "Default")
      (node (ref "CE0") (pin "50") (pinfunction "D7_50") (pintype "bidirectional"))
      (node (ref "U16") (pin "9") (pinfunction "A8_9") (pintype "bidirectional"))
    )
    (net (code "69") (name "Net-(CF1A-IORDY)") (class "Default")
      (node (ref "CF1") (pin "42") (pinfunction "IORDY_42") (pintype "output"))
      (node (ref "JP4") (pin "2") (pinfunction "2_2") (pintype "passive"))
    )
    (net (code "70") (name "Net-(CF1A-~{DASP})") (class "Default")
      (node (ref "CF1") (pin "45") (pinfunction "~{DASP}_45") (pintype "open_collector"))
      (node (ref "D2") (pin "C") (pinfunction "C_C") (pintype "passive"))
    )
    (net (code "71") (name "Net-(CF1A-~{PDIAG})") (class "Default")
      (node (ref "CF1") (pin "46") (pinfunction "~{PDIAG}_46") (pintype "output"))
      (node (ref "R12") (pin "1") (pinfunction "1_1") (pintype "passive"))
    )
    (net (code "72") (name "Net-(D1-PadA)") (class "Default")
      (node (ref "D1") (pin "A") (pinfunction "A_A") (pintype "passive"))
      (node (ref "R1") (pin "1") (pinfunction "1_1") (pintype "passive"))
    )
    (net (code "73") (name "Net-(D2-PadA)") (class "Default")
      (node (ref "D2") (pin "A") (pinfunction "A_A") (pintype "passive"))
      (node (ref "R11") (pin "1") (pinfunction "1_1") (pintype "passive"))
    )
    (net (code "74") (name "Net-(JP8-Pad1)") (class "Default")
      (node (ref "JP8") (pin "1") (pinfunction "1_1") (pintype "passive"))
      (node (ref "R8") (pin "2") (pinfunction "2_2") (pintype "passive"))
      (node (ref "S2") (pin "3") (pinfunction "3_3") (pintype "passive"))
    )
    (net (code "75") (name "Net-(JP10-Pad1)") (class "Default")
      (node (ref "JP10") (pin "1") (pinfunction "1_1") (pintype "passive"))
      (node (ref "R9") (pin "2") (pinfunction "2_2") (pintype "passive"))
      (node (ref "S2") (pin "2") (pinfunction "2_2") (pintype "passive"))
    )
    (net (code "76") (name "Net-(JP12-Pad1)") (class "Default")
      (node (ref "JP12") (pin "1") (pinfunction "1_1") (pintype "passive"))
      (node (ref "R10") (pin "2") (pinfunction "2_2") (pintype "passive"))
      (node (ref "S2") (pin "1") (pinfunction "1_1") (pintype "passive"))
    )
    (net (code "77") (name "Net-(Q1-B)") (class "Default")
      (node (ref "Q1") (pin "2") (pinfunction "B_2") (pintype "passive"))
      (node (ref "R2") (pin "2") (pinfunction "2_2") (pintype "passive"))
    )
    (net (code "78") (name "Net-(Q1-C)") (class "Default")
      (node (ref "Q1") (pin "3") (pinfunction "C_3") (pintype "passive"))
      (node (ref "R1") (pin "2") (pinfunction "2_2") (pintype "passive"))
    )
    (net (code "79") (name "Net-(U1A-A12)") (class "Default")
      (node (ref "JP8") (pin "2") (pinfunction "2_2") (pintype "passive"))
      (node (ref "U1") (pin "2") (pinfunction "A12_2") (pintype "input"))
    )
    (net (code "80") (name "Net-(U1A-A13)") (class "Default")
      (node (ref "JP10") (pin "2") (pinfunction "2_2") (pintype "passive"))
      (node (ref "U1") (pin "26") (pinfunction "A13_26") (pintype "input"))
    )
    (net (code "81") (name "Net-(U1A-A14)") (class "Default")
      (node (ref "JP12") (pin "2") (pinfunction "2_2") (pintype "passive"))
      (node (ref "U1") (pin "1") (pinfunction "A14_1") (pintype "input"))
    )
    (net (code "82") (name "Net-(U2A-~{CE})") (class "Default")
      (node (ref "JP6") (pin "2") (pinfunction "2_2") (pintype "passive"))
      (node (ref "U2") (pin "22") (pinfunction "~{CE}_22") (pintype "input"))
    )
    (net (code "83") (name "Net-(U2B-VCC)") (class "Default")
      (node (ref "C2") (pin "1") (pinfunction "1_1") (pintype "passive"))
      (node (ref "JP7") (pin "2") (pinfunction "2_2") (pintype "passive"))
      (node (ref "U2") (pin "32") (pinfunction "VCC_32") (pintype "power_in"))
    )
    (net (code "84") (name "Net-(U3A-~{CE})") (class "Default")
      (node (ref "U3") (pin "22") (pinfunction "~{CE}_22") (pintype "input"))
      (node (ref "U7") (pin "6") (pinfunction "O_6") (pintype "output"))
    )
    (net (code "85") (name "Net-(U4A-BC)") (class "Default")
      (node (ref "BT1") (pin "+") (pinfunction "+_+") (pintype "passive"))
      (node (ref "U4") (pin "24") (pinfunction "BC_24") (pintype "input"))
    )
    (net (code "86") (name "Net-(U4A-VCC)") (class "Default")
      (node (ref "C4") (pin "1") (pinfunction "1_1") (pintype "passive"))
      (node (ref "JP14") (pin "2") (pinfunction "2_2") (pintype "passive"))
      (node (ref "U4") (pin "28") (pinfunction "VCC_28") (pintype "input"))
    )
    (net (code "87") (name "Net-(U4A-WDI)") (class "Default")
      (node (ref "JP1") (pin "2") (pinfunction "2_2") (pintype "passive"))
      (node (ref "U4") (pin "23") (pinfunction "WDI_23") (pintype "input"))
    )
    (net (code "88") (name "Net-(U4A-X1)") (class "Default")
      (node (ref "U4") (pin "2") (pinfunction "X1_2") (pintype "input"))
      (node (ref "Y1") (pin "2") (pinfunction "2_2") (pintype "passive"))
    )
    (net (code "89") (name "Net-(U4A-X2)") (class "Default")
      (node (ref "U4") (pin "3") (pinfunction "X2_3") (pintype "input"))
      (node (ref "Y1") (pin "1") (pinfunction "1_1") (pintype "passive"))
    )
    (net (code "90") (name "Net-(U4A-~{RST})") (class "Default")
      (node (ref "JP2") (pin "1") (pinfunction "1_1") (pintype "passive"))
      (node (ref "U4") (pin "6") (pinfunction "~{RST}_6") (pintype "open_collector"))
    )
    (net (code "91") (name "Net-(U4A-~{WDO})") (class "Default")
      (node (ref "R2") (pin "1") (pinfunction "1_1") (pintype "passive"))
      (node (ref "U4") (pin "4") (pinfunction "~{WDO}_4") (pintype "output"))
    )
    (net (code "92") (name "Net-(U5A-G)") (class "Default")
      (node (ref "U5") (pin "1") (pinfunction "G_1") (pintype "input"))
      (node (ref "U8") (pin "2") (pinfunction "O_2") (pintype "output"))
    )
    (net (code "93") (name "Net-(U5A-P0)") (class "Default")
      (node (ref "JP9") (pin "2") (pinfunction "2_2") (pintype "passive"))
      (node (ref "U5") (pin "2") (pinfunction "P0_2") (pintype "input"))
    )
    (net (code "94") (name "Net-(U5A-P1)") (class "Default")
      (node (ref "JP13") (pin "2") (pinfunction "2_2") (pintype "passive"))
      (node (ref "U5") (pin "4") (pinfunction "P1_4") (pintype "input"))
    )
    (net (code "95") (name "Net-(U5A-P7)") (class "Default")
      (node (ref "JP11") (pin "2") (pinfunction "2_2") (pintype "passive"))
      (node (ref "U5") (pin "17") (pinfunction "P7_17") (pintype "input"))
    )
    (net (code "96") (name "Net-(U6A-I0)") (class "Default")
      (node (ref "U6") (pin "1") (pinfunction "I0_1") (pintype "input"))
      (node (ref "U8") (pin "12") (pinfunction "O_12") (pintype "output"))
    )
    (net (code "97") (name "Net-(U7A-I0)") (class "Default")
      (node (ref "U7") (pin "1") (pinfunction "I0_1") (pintype "input"))
      (node (ref "U8") (pin "6") (pinfunction "O_6") (pintype "output"))
    )
    (net (code "98") (name "Net-(U7C-O)") (class "Default")
      (node (ref "U7") (pin "8") (pinfunction "O_8") (pintype "output"))
      (node (ref "U8") (pin "9") (pinfunction "I_9") (pintype "input"))
    )
    (net (code "99") (name "Net-(U8B-I)") (class "Default")
      (node (ref "JP5") (pin "2") (pinfunction "2_2") (pintype "passive"))
      (node (ref "R7") (pin "2") (pinfunction "2_2") (pintype "passive"))
      (node (ref "U8") (pin "3") (pinfunction "I_3") (pintype "input"))
    )
    (net (code "100") (name "Net-(U16A-G)") (class "Default")
      (node (ref "U16") (pin "19") (pinfunction "G_19") (pintype "input"))
      (node (ref "U6") (pin "3") (pinfunction "O_3") (pintype "output"))
    )
    (net (code "101") (name "SW12") (class "Default")
      (node (ref "JP9") (pin "3") (pinfunction "3_3") (pintype "passive"))
      (node (ref "RN1") (pin "2") (pinfunction "2_2") (pintype "passive"))
      (node (ref "S1") (pin "8") (pinfunction "8_8") (pintype "passive"))
      (node (ref "U5") (pin "3") (pinfunction "Q0_3") (pintype "input"))
    )
    (net (code "102") (name "SW13") (class "Default")
      (node (ref "JP11") (pin "3") (pinfunction "3_3") (pintype "passive"))
      (node (ref "RN1") (pin "3") (pinfunction "3_3") (pintype "passive"))
      (node (ref "S1") (pin "7") (pinfunction "7_7") (pintype "passive"))
      (node (ref "U5") (pin "18") (pinfunction "Q7_18") (pintype "input"))
    )
    (net (code "103") (name "SW14") (class "Default")
      (node (ref "JP13") (pin "3") (pinfunction "3_3") (pintype "passive"))
      (node (ref "RN1") (pin "4") (pinfunction "4_4") (pintype "passive"))
      (node (ref "S1") (pin "6") (pinfunction "6_6") (pintype "passive"))
      (node (ref "U5") (pin "5") (pinfunction "Q1_5") (pintype "input"))
    )
    (net (code "104") (name "SW15") (class "Default")
      (node (ref "RN1") (pin "5") (pinfunction "5_5") (pintype "passive"))
      (node (ref "S1") (pin "5") (pinfunction "5_5") (pintype "passive"))
      (node (ref "U5") (pin "16") (pinfunction "Q6_16") (pintype "input"))
    )
    (net (code "105") (name "SW16") (class "Default")
      (node (ref "RN1") (pin "6") (pinfunction "6_6") (pintype "passive"))
      (node (ref "S1") (pin "4") (pinfunction "4_4") (pintype "passive"))
      (node (ref "U5") (pin "7") (pinfunction "Q2_7") (pintype "input"))
    )
    (net (code "106") (name "SW17") (class "Default")
      (node (ref "RN1") (pin "7") (pinfunction "7_7") (pintype "passive"))
      (node (ref "S1") (pin "3") (pinfunction "3_3") (pintype "passive"))
      (node (ref "U5") (pin "14") (pinfunction "Q5_14") (pintype "input"))
    )
    (net (code "107") (name "SW18") (class "Default")
      (node (ref "RN1") (pin "8") (pinfunction "8_8") (pintype "passive"))
      (node (ref "S1") (pin "2") (pinfunction "2_2") (pintype "passive"))
      (node (ref "U5") (pin "9") (pinfunction "Q3_9") (pintype "input"))
    )
    (net (code "108") (name "SW19") (class "Default")
      (node (ref "RN1") (pin "9") (pinfunction "9_9") (pintype "passive"))
      (node (ref "S1") (pin "1") (pinfunction "1_1") (pintype "passive"))
      (node (ref "U5") (pin "12") (pinfunction "Q4_12") (pintype "input"))
    )
    (net (code "109") (name "VBAT") (class "Default")
      (node (ref "JP7") (pin "3") (pinfunction "3_3") (pintype "passive"))
      (node (ref "U4") (pin "1") (pinfunction "VOUT_1") (pintype "input"))
    )
    (net (code "110") (name "VCC") (class "Default")
      (node (ref "C1") (pin "1") (pinfunction "1_1") (pintype "passive"))
      (node (ref "C10") (pin "1") (pinfunction "1_1") (pintype "passive"))
      (node (ref "C11") (pin "1") (pinfunction "1_1") (pintype "passive"))
      (node (ref "C12") (pin "1") (pinfunction "1_1") (pintype "passive"))
      (node (ref "C13") (pin "1") (pinfunction "1_1") (pintype "passive"))
      (node (ref "C14") (pin "1") (pinfunction "1_1") (pintype "passive"))
      (node (ref "C15") (pin "1") (pinfunction "1_1") (pintype "passive"))
      (node (ref "C16") (pin "1") (pinfunction "1_1") (pintype "passive"))
      (node (ref "C17") (pin "1") (pinfunction "1_1") (pintype "passive"))
      (node (ref "C18") (pin "1") (pinfunction "1_1") (pintype "passive"))
      (node (ref "C19") (pin "+") (pinfunction "+_+") (pintype "passive"))
      (node (ref "C3") (pin "1") (pinfunction "1_1") (pintype "passive"))
      (node (ref "C5") (pin "1") (pinfunction "1_1") (pintype "passive"))
      (node (ref "C6") (pin "1") (pinfunction "1_1") (pintype "passive"))
      (node (ref "C7") (pin "1") (pinfunction "1_1") (pintype "passive"))
      (node (ref "C8") (pin "1") (pinfunction "1_1") (pintype "passive"))
      (node (ref "C9") (pin "1") (pinfunction "1_1") (pintype "passive"))
      (node (ref "CE0") (pin "5") (pinfunction "+5V_5") (pintype "bidirectional"))
      (node (ref "CE0") (pin "6") (pinfunction "+5V_6") (pintype "bidirectional"))
      (node (ref "CF1") (pin "32") (pinfunction "~{CS1}_32") (pintype "input"))
      (node (ref "CF1") (pin "36") (pinfunction "~{WE}_36") (pintype "input"))
      (node (ref "CF1") (pin "44") (pinfunction "~{DMACK}_44") (pintype "input"))
      (node (ref "JP14") (pin "3") (pinfunction "3_3") (pintype "passive"))
      (node (ref "JP7") (pin "1") (pinfunction "1_1") (pintype "passive"))
      (node (ref "Q1") (pin "1") (pinfunction "E_1") (pintype "passive"))
      (node (ref "R11") (pin "2") (pinfunction "2_2") (pintype "passive"))
      (node (ref "R12") (pin "2") (pinfunction "2_2") (pintype "passive"))
      (node (ref "R3") (pin "1") (pinfunction "1_1") (pintype "passive"))
      (node (ref "R4") (pin "2") (pinfunction "2_2") (pintype "passive"))
      (node (ref "R5") (pin "1") (pinfunction "1_1") (pintype "passive"))
      (node (ref "R6") (pin "1") (pinfunction "1_1") (pintype "passive"))
      (node (ref "RN2") (pin "1") (pinfunction "1_1") (pintype "passive"))
      (node (ref "S1") (pin "10") (pinfunction "10_10") (pintype "passive"))
      (node (ref "S1") (pin "11") (pinfunction "11_11") (pintype "passive"))
      (node (ref "S1") (pin "12") (pinfunction "12_12") (pintype "passive"))
      (node (ref "S1") (pin "13") (pinfunction "13_13") (pintype "passive"))
      (node (ref "S1") (pin "14") (pinfunction "14_14") (pintype "passive"))
      (node (ref "S1") (pin "15") (pinfunction "15_15") (pintype "passive"))
      (node (ref "S1") (pin "16") (pinfunction "16_16") (pintype "passive"))
      (node (ref "S1") (pin "9") (pinfunction "9_9") (pintype "passive"))
      (node (ref "S2") (pin "4") (pinfunction "4_4") (pintype "passive"))
      (node (ref "S2") (pin "5") (pinfunction "5_5") (pintype "passive"))
      (node (ref "S2") (pin "6") (pinfunction "6_6") (pintype "passive"))
      (node (ref "U1") (pin "27") (pinfunction "~{WE}_27") (pintype "input"))
      (node (ref "U11") (pin "6") (pinfunction "G1_6") (pintype "input"))
      (node (ref "U13") (pin "2") (pinfunction "A1_2") (pintype "input"))
      (node (ref "U6") (pin "10") (pinfunction "I1_10") (pintype "input"))
      (node (ref "U6") (pin "12") (pinfunction "I0_12") (pintype "input"))
      (node (ref "U6") (pin "13") (pinfunction "I1_13") (pintype "input"))
      (node (ref "U6") (pin "4") (pinfunction "I0_4") (pintype "input"))
      (node (ref "U6") (pin "5") (pinfunction "I1_5") (pintype "input"))
      (node (ref "U6") (pin "9") (pinfunction "I0_9") (pintype "input"))
      (node (ref "U7") (pin "9") (pinfunction "I0_9") (pintype "input"))
      (node (ref "U8") (pin "11") (pinfunction "I_11") (pintype "input"))
      (node (ref "U9") (pin "11") (pinfunction "A1_11") (pintype "input"))
      (node (ref "U9") (pin "13") (pinfunction "A2_13") (pintype "input"))
      (node (ref "U9") (pin "6") (pinfunction "A3_6") (pintype "input"))
      (node (ref "U9") (pin "8") (pinfunction "A4_8") (pintype "input"))
    )
    (net (code "111") (name "unconnected-(CE0-+3.3V-Pad2)") (class "Default")
      (node (ref "CE0") (pin "2") (pinfunction "+3.3V_2") (pintype "bidirectional"))
    )
    (net (code "112") (name "unconnected-(CE0-+12V-Pad1)") (class "Default")
      (node (ref "CE0") (pin "1") (pinfunction "+12V_1") (pintype "bidirectional"))
    )
    (net (code "113") (name "unconnected-(CE0--12V-Pad7)") (class "Default")
      (node (ref "CE0") (pin "7") (pinfunction "-12V_7") (pintype "bidirectional"))
    )
    (net (code "114") (name "unconnected-(CE0-CLK-Pad15)") (class "Default")
      (node (ref "CE0") (pin "15") (pinfunction "CLK_15") (pintype "bidirectional"))
    )
    (net (code "115") (name "unconnected-(CE0-CLKAUX-Pad16)") (class "Default")
      (node (ref "CE0") (pin "16") (pinfunction "CLKAUX_16") (pintype "bidirectional"))
    )
    (net (code "116") (name "unconnected-(CE0-~{BUSACK}-Pad20)") (class "Default")
      (node (ref "CE0") (pin "20") (pinfunction "~{BUSACK}_20") (pintype "bidirectional"))
    )
    (net (code "117") (name "unconnected-(CE0-~{BUSRQ}-Pad10)") (class "Default")
      (node (ref "CE0") (pin "10") (pinfunction "~{BUSRQ}_10") (pintype "bidirectional"))
    )
    (net (code "118") (name "unconnected-(CE0-~{CBR}-Pad12)") (class "Default")
      (node (ref "CE0") (pin "12") (pinfunction "~{CBR}_12") (pintype "bidirectional"))
    )
    (net (code "119") (name "unconnected-(CE0-~{FETCH}-Pad19)") (class "Default")
      (node (ref "CE0") (pin "19") (pinfunction "~{FETCH}_19") (pintype "bidirectional"))
    )
    (net (code "120") (name "unconnected-(CE0-~{HALT}-Pad17)") (class "Default")
      (node (ref "CE0") (pin "17") (pinfunction "~{HALT}_17") (pintype "bidirectional"))
    )
    (net (code "121") (name "unconnected-(CE0-~{INH}-Pad11)") (class "Default")
      (node (ref "CE0") (pin "11") (pinfunction "~{INH}_11") (pintype "bidirectional"))
    )
    (net (code "122") (name "unconnected-(CE0-~{INT}-Pad51)") (class "Default")
      (node (ref "CE0") (pin "51") (pinfunction "~{INT}_51") (pintype "bidirectional"))
    )
    (net (code "123") (name "unconnected-(CE0-~{IRQ0}-Pad53)") (class "Default")
      (node (ref "CE0") (pin "53") (pinfunction "~{IRQ0}_53") (pintype "bidirectional"))
    )
    (net (code "124") (name "unconnected-(CE0-~{IRQ1}-Pad54)") (class "Default")
      (node (ref "CE0") (pin "54") (pinfunction "~{IRQ1}_54") (pintype "bidirectional"))
    )
    (net (code "125") (name "unconnected-(CE0-~{IRQ2}-Pad55)") (class "Default")
      (node (ref "CE0") (pin "55") (pinfunction "~{IRQ2}_55") (pintype "bidirectional"))
    )
    (net (code "126") (name "unconnected-(CE0-~{IRQ3}-Pad56)") (class "Default")
      (node (ref "CE0") (pin "56") (pinfunction "~{IRQ3}_56") (pintype "bidirectional"))
    )
    (net (code "127") (name "unconnected-(CE0-~{IRQ4}-Pad57)") (class "Default")
      (node (ref "CE0") (pin "57") (pinfunction "~{IRQ4}_57") (pintype "bidirectional"))
    )
    (net (code "128") (name "unconnected-(CE0-~{IRQ5}-Pad58)") (class "Default")
      (node (ref "CE0") (pin "58") (pinfunction "~{IRQ5}_58") (pintype "bidirectional"))
    )
    (net (code "129") (name "unconnected-(CE0-~{IRQ6}-Pad59)") (class "Default")
      (node (ref "CE0") (pin "59") (pinfunction "~{IRQ6}_59") (pintype "bidirectional"))
    )
    (net (code "130") (name "unconnected-(CE0-~{IRQ7}-Pad60)") (class "Default")
      (node (ref "CE0") (pin "60") (pinfunction "~{IRQ7}_60") (pintype "bidirectional"))
    )
    (net (code "131") (name "unconnected-(CE0-~{NMI}-Pad61)") (class "Default")
      (node (ref "CE0") (pin "61") (pinfunction "~{NMI}_61") (pintype "bidirectional"))
    )
    (net (code "132") (name "unconnected-(CF1A-D08-Pad47)") (class "Default")
      (node (ref "CF1") (pin "47") (pinfunction "D08_47") (pintype "tri_state"))
    )
    (net (code "133") (name "unconnected-(CF1A-D09-Pad48)") (class "Default")
      (node (ref "CF1") (pin "48") (pinfunction "D09_48") (pintype "tri_state"))
    )
    (net (code "134") (name "unconnected-(CF1A-D10-Pad49)") (class "Default")
      (node (ref "CF1") (pin "49") (pinfunction "D10_49") (pintype "tri_state"))
    )
    (net (code "135") (name "unconnected-(CF1A-D11-Pad27)") (class "Default")
      (node (ref "CF1") (pin "27") (pinfunction "D11_27") (pintype "tri_state"))
    )
    (net (code "136") (name "unconnected-(CF1A-D12-Pad28)") (class "Default")
      (node (ref "CF1") (pin "28") (pinfunction "D12_28") (pintype "tri_state"))
    )
    (net (code "137") (name "unconnected-(CF1A-D13-Pad29)") (class "Default")
      (node (ref "CF1") (pin "29") (pinfunction "D13_29") (pintype "tri_state"))
    )
    (net (code "138") (name "unconnected-(CF1A-D14-Pad30)") (class "Default")
      (node (ref "CF1") (pin "30") (pinfunction "D14_30") (pintype "tri_state"))
    )
    (net (code "139") (name "unconnected-(CF1A-D15-Pad31)") (class "Default")
      (node (ref "CF1") (pin "31") (pinfunction "D15_31") (pintype "tri_state"))
    )
    (net (code "140") (name "unconnected-(CF1A-DMARQ-Pad43)") (class "Default")
      (node (ref "CF1") (pin "43") (pinfunction "DMARQ_43") (pintype "output"))
    )
    (net (code "141") (name "unconnected-(CF1A-~{IOCS16}-Pad24)") (class "Default")
      (node (ref "CF1") (pin "24") (pinfunction "~{IOCS16}_24") (pintype "output"))
    )
    (net (code "142") (name "unconnected-(CF1A-~{VS1}-Pad33)") (class "Default")
      (node (ref "CF1") (pin "33") (pinfunction "~{VS1}_33") (pintype "output"))
    )
    (net (code "143") (name "unconnected-(CF1A-~{VS2}-Pad40)") (class "Default")
      (node (ref "CF1") (pin "40") (pinfunction "~{VS2}_40") (pintype "output"))
    )
    (net (code "144") (name "unconnected-(U6B-O-Pad6)") (class "Default")
      (node (ref "U6") (pin "6") (pinfunction "O_6") (pintype "output"))
    )
    (net (code "145") (name "unconnected-(U6C-O-Pad8)") (class "Default")
      (node (ref "U6") (pin "8") (pinfunction "O_8") (pintype "output"))
    )
    (net (code "146") (name "unconnected-(U6D-O-Pad11)") (class "Default")
      (node (ref "U6") (pin "11") (pinfunction "O_11") (pintype "output"))
    )
    (net (code "147") (name "unconnected-(U8E-O-Pad10)") (class "Default")
      (node (ref "U8") (pin "10") (pinfunction "O_10") (pintype "output"))
    )
    (net (code "148") (name "unconnected-(U11A-Y2-Pad13)") (class "Default")
      (node (ref "U11") (pin "13") (pinfunction "Y2_13") (pintype "output"))
    )
    (net (code "149") (name "unconnected-(U11A-Y3-Pad12)") (class "Default")
      (node (ref "U11") (pin "12") (pinfunction "Y3_12") (pintype "output"))
    )
    (net (code "150") (name "unconnected-(U11A-Y4-Pad11)") (class "Default")
      (node (ref "U11") (pin "11") (pinfunction "Y4_11") (pintype "output"))
    )
    (net (code "151") (name "unconnected-(U11A-Y5-Pad10)") (class "Default")
      (node (ref "U11") (pin "10") (pinfunction "Y5_10") (pintype "output"))
    )
    (net (code "152") (name "unconnected-(U11A-Y6-Pad9)") (class "Default")
      (node (ref "U11") (pin "9") (pinfunction "Y6_9") (pintype "output"))
    )
    (net (code "153") (name "unconnected-(U11A-Y7-Pad7)") (class "Default")
      (node (ref "U11") (pin "7") (pinfunction "Y7_7") (pintype "output"))
    )
    (net (code "154") (name "unconnected-(U12A-Y0-Pad15)") (class "Default")
      (node (ref "U12") (pin "15") (pinfunction "Y0_15") (pintype "output"))
    )
    (net (code "155") (name "unconnected-(U12A-Y1-Pad14)") (class "Default")
      (node (ref "U12") (pin "14") (pinfunction "Y1_14") (pintype "output"))
    )
    (net (code "156") (name "unconnected-(U12A-Y2-Pad13)") (class "Default")
      (node (ref "U12") (pin "13") (pinfunction "Y2_13") (pintype "output"))
    )
    (net (code "157") (name "unconnected-(U12A-Y3-Pad12)") (class "Default")
      (node (ref "U12") (pin "12") (pinfunction "Y3_12") (pintype "output"))
    )
    (net (code "158") (name "unconnected-(U12A-Y5-Pad10)") (class "Default")
      (node (ref "U12") (pin "10") (pinfunction "Y5_10") (pintype "output"))
    )
    (net (code "159") (name "unconnected-(U12A-Y6-Pad9)") (class "Default")
      (node (ref "U12") (pin "9") (pinfunction "Y6_9") (pintype "output"))
    )
    (net (code "160") (name "unconnected-(U13A-Y1-Pad18)") (class "Default")
      (node (ref "U13") (pin "18") (pinfunction "Y1_18") (pintype "tri_state"))
    )
    (net (code "161") (name "~{BCSX}") (class "Default")
      (node (ref "CE0") (pin "9") (pinfunction "~{CSX}_9") (pintype "bidirectional"))
      (node (ref "U13") (pin "17") (pinfunction "A4_17") (pintype "input"))
    )
    (net (code "162") (name "~{BRD}") (class "Default")
      (node (ref "CE0") (pin "21") (pinfunction "~{RD}_21") (pintype "bidirectional"))
      (node (ref "U13") (pin "4") (pinfunction "A2_4") (pintype "input"))
    )
    (net (code "163") (name "~{BWR}") (class "Default")
      (node (ref "CE0") (pin "22") (pinfunction "~{WR}_22") (pintype "bidirectional"))
      (node (ref "U13") (pin "6") (pinfunction "A3_6") (pintype "input"))
    )
    (net (code "164") (name "~{CESB}IN") (class "Default")
      (node (ref "JP6") (pin "1") (pinfunction "1_1") (pintype "passive"))
      (node (ref "U4") (pin "26") (pinfunction "~{CEIN}_26") (pintype "input"))
      (node (ref "U7") (pin "12") (pinfunction "O_12") (pintype "output"))
    )
    (net (code "165") (name "~{CESB}OUT") (class "Default")
      (node (ref "JP6") (pin "3") (pinfunction "3_3") (pintype "passive"))
      (node (ref "U4") (pin "25") (pinfunction "~{CEOUT}_25") (pintype "output"))
    )
    (net (code "166") (name "~{CF_CD1}") (class "Default")
      (node (ref "CF1") (pin "26") (pinfunction "~{CD1}_26") (pintype "output"))
      (node (ref "R6") (pin "2") (pinfunction "2_2") (pintype "passive"))
      (node (ref "U9") (pin "4") (pinfunction "A2_4") (pintype "input"))
    )
    (net (code "167") (name "~{CF_CD2}") (class "Default")
      (node (ref "CF1") (pin "25") (pinfunction "~{CD2}_25") (pintype "output"))
      (node (ref "R5") (pin "2") (pinfunction "2_2") (pintype "passive"))
      (node (ref "U9") (pin "15") (pinfunction "A3_15") (pintype "input"))
    )
    (net (code "168") (name "~{CINH}") (class "Default")
      (node (ref "CE0") (pin "13") (pinfunction "~{CINH}_13") (pintype "bidirectional"))
      (node (ref "U7") (pin "13") (pinfunction "I2_13") (pintype "input"))
      (node (ref "U7") (pin "5") (pinfunction "I2_5") (pintype "input"))
      (node (ref "U8") (pin "1") (pinfunction "I_1") (pintype "input"))
      (node (ref "U8") (pin "13") (pinfunction "I_13") (pintype "input"))
    )
    (net (code "169") (name "~{CSX}") (class "Default")
      (node (ref "U11") (pin "4") (pinfunction "G2A_4") (pintype "input"))
      (node (ref "U12") (pin "4") (pinfunction "G2A_4") (pintype "input"))
      (node (ref "U13") (pin "3") (pinfunction "Y4_3") (pintype "tri_state"))
      (node (ref "U6") (pin "2") (pinfunction "I1_2") (pintype "input"))
    )
    (net (code "170") (name "~{CS_CF}") (class "Default")
      (node (ref "CF1") (pin "7") (pinfunction "~{CS0}_7") (pintype "input"))
      (node (ref "U11") (pin "15") (pinfunction "Y0_15") (pintype "output"))
    )
    (net (code "171") (name "~{CS_ID}") (class "Default")
      (node (ref "U10") (pin "1") (pinfunction "G_1") (pintype "input"))
      (node (ref "U10") (pin "19") (pinfunction "G_19") (pintype "input"))
      (node (ref "U12") (pin "7") (pinfunction "Y7_7") (pintype "output"))
    )
    (net (code "172") (name "~{CS_RTC}") (class "Default")
      (node (ref "U11") (pin "14") (pinfunction "Y1_14") (pintype "output"))
      (node (ref "U4") (pin "21") (pinfunction "~{CS}_21") (pintype "input"))
    )
    (net (code "173") (name "~{CS_SR}") (class "Default")
      (node (ref "U12") (pin "11") (pinfunction "Y4_11") (pintype "output"))
      (node (ref "U9") (pin "1") (pinfunction "G_1") (pintype "input"))
      (node (ref "U9") (pin "19") (pinfunction "G_19") (pintype "input"))
    )
    (net (code "174") (name "~{INT_RTC}") (class "Default")
      (node (ref "JP3") (pin "1") (pinfunction "1_1") (pintype "passive"))
      (node (ref "U4") (pin "5") (pinfunction "~{INT}_5") (pintype "open_collector"))
    )
    (net (code "175") (name "~{IRQX}") (class "Default")
      (node (ref "CE0") (pin "52") (pinfunction "~{IRQX}_52") (pintype "bidirectional"))
      (node (ref "U8") (pin "8") (pinfunction "O_8") (pintype "output"))
    )
    (net (code "176") (name "~{RD}") (class "Default")
      (node (ref "CF1") (pin "34") (pinfunction "~{IORD}_34") (pintype "input"))
      (node (ref "U1") (pin "22") (pinfunction "~{OE}_22") (pintype "input"))
      (node (ref "U12") (pin "5") (pinfunction "G2B_5") (pintype "input"))
      (node (ref "U13") (pin "16") (pinfunction "Y2_16") (pintype "tri_state"))
      (node (ref "U16") (pin "1") (pinfunction "DIR_1") (pintype "input"))
      (node (ref "U2") (pin "24") (pinfunction "~{OE}_24") (pintype "input"))
      (node (ref "U3") (pin "24") (pinfunction "~{OE}_24") (pintype "input"))
      (node (ref "U4") (pin "22") (pinfunction "~{OE}_22") (pintype "input"))
    )
    (net (code "177") (name "~{RST}") (class "Default")
      (node (ref "CE0") (pin "14") (pinfunction "~{RST}_14") (pintype "bidirectional"))
      (node (ref "CF1") (pin "41") (pinfunction "/RESET_41") (pintype "input"))
      (node (ref "JP2") (pin "2") (pinfunction "2_2") (pintype "passive"))
    )
    (net (code "178") (name "~{SR_CF}") (class "Default")
      (node (ref "U7") (pin "11") (pinfunction "I2_11") (pintype "input"))
      (node (ref "U8") (pin "4") (pinfunction "O_4") (pintype "output"))
      (node (ref "U9") (pin "2") (pinfunction "A1_2") (pintype "input"))
    )
    (net (code "179") (name "~{SR_RTC}") (class "Default")
      (node (ref "JP3") (pin "2") (pinfunction "2_2") (pintype "passive"))
      (node (ref "R4") (pin "1") (pinfunction "1_1") (pintype "passive"))
      (node (ref "U7") (pin "10") (pinfunction "I1_10") (pintype "input"))
      (node (ref "U9") (pin "17") (pinfunction "A4_17") (pintype "input"))
    )
    (net (code "180") (name "~{U3CS}") (class "Default")
      (node (ref "R3") (pin "2") (pinfunction "2_2") (pintype "passive"))
      (node (ref "U1") (pin "20") (pinfunction "~{CE}_20") (pintype "input"))
      (node (ref "U5") (pin "19") (pinfunction "P=Q_19") (pintype "output"))
      (node (ref "U7") (pin "2") (pinfunction "I1_2") (pintype "input"))
      (node (ref "U7") (pin "4") (pinfunction "I1_4") (pintype "input"))
    )
    (net (code "181") (name "~{WAIT}") (class "Default")
      (node (ref "CE0") (pin "18") (pinfunction "~{WAIT}_18") (pintype "bidirectional"))
      (node (ref "JP4") (pin "1") (pinfunction "1_1") (pintype "passive"))
    )
    (net (code "182") (name "~{WR}") (class "Default")
      (node (ref "CF1") (pin "35") (pinfunction "~{IOWR}_35") (pintype "input"))
      (node (ref "U13") (pin "14") (pinfunction "Y3_14") (pintype "tri_state"))
      (node (ref "U2") (pin "29") (pinfunction "~{WE}_29") (pintype "input"))
      (node (ref "U3") (pin "29") (pinfunction "~{WE}_29") (pintype "input"))
      (node (ref "U4") (pin "27") (pinfunction "~{WE}_27") (pintype "input"))
    )
  )
)
